# 20160428.net
KiCad netlist of a schematic drawn in Altium Designer
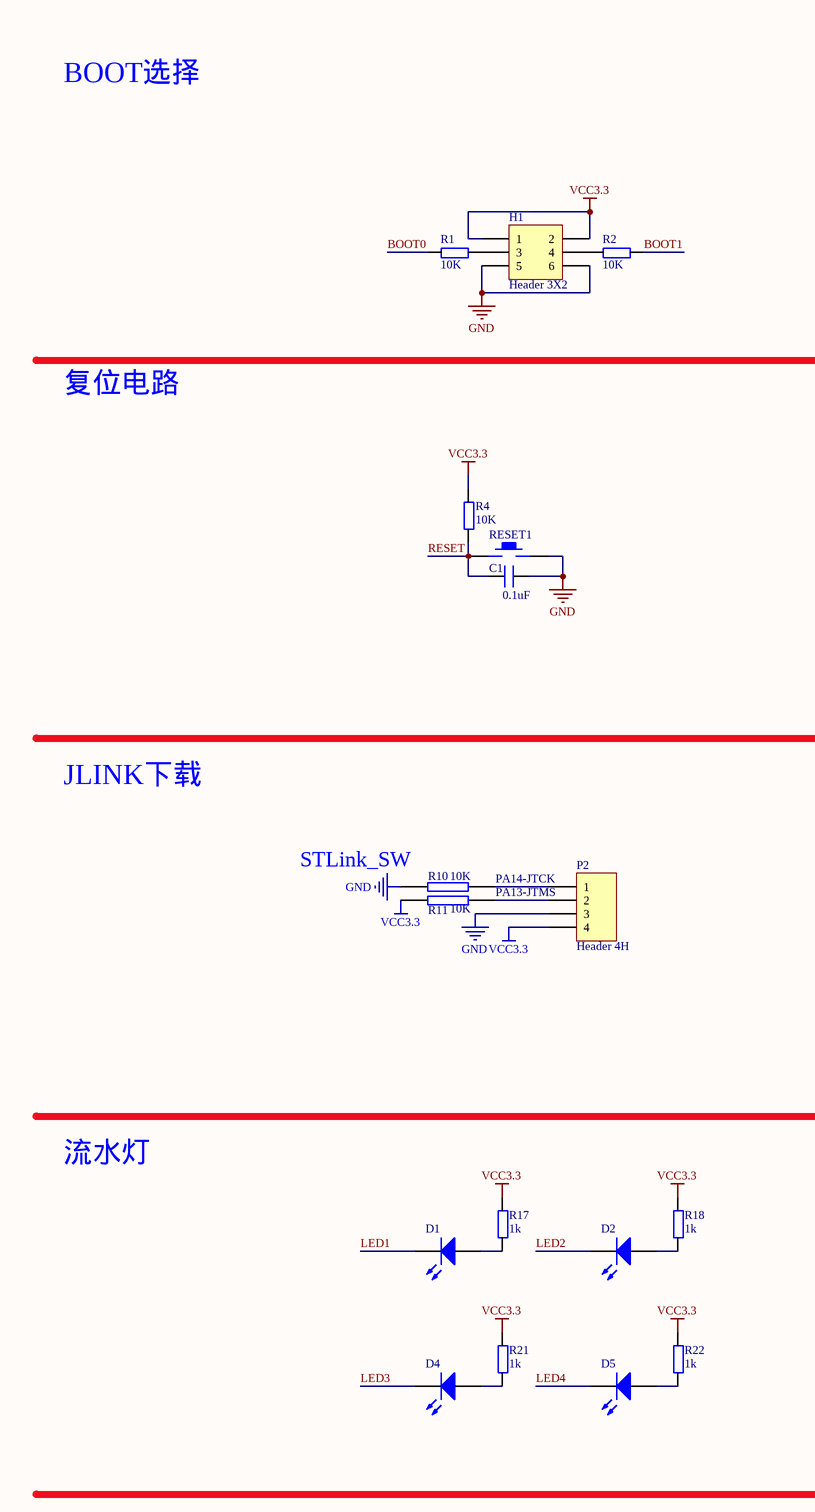
[diagram p0: 主控板20160428.SchDoc, top left]
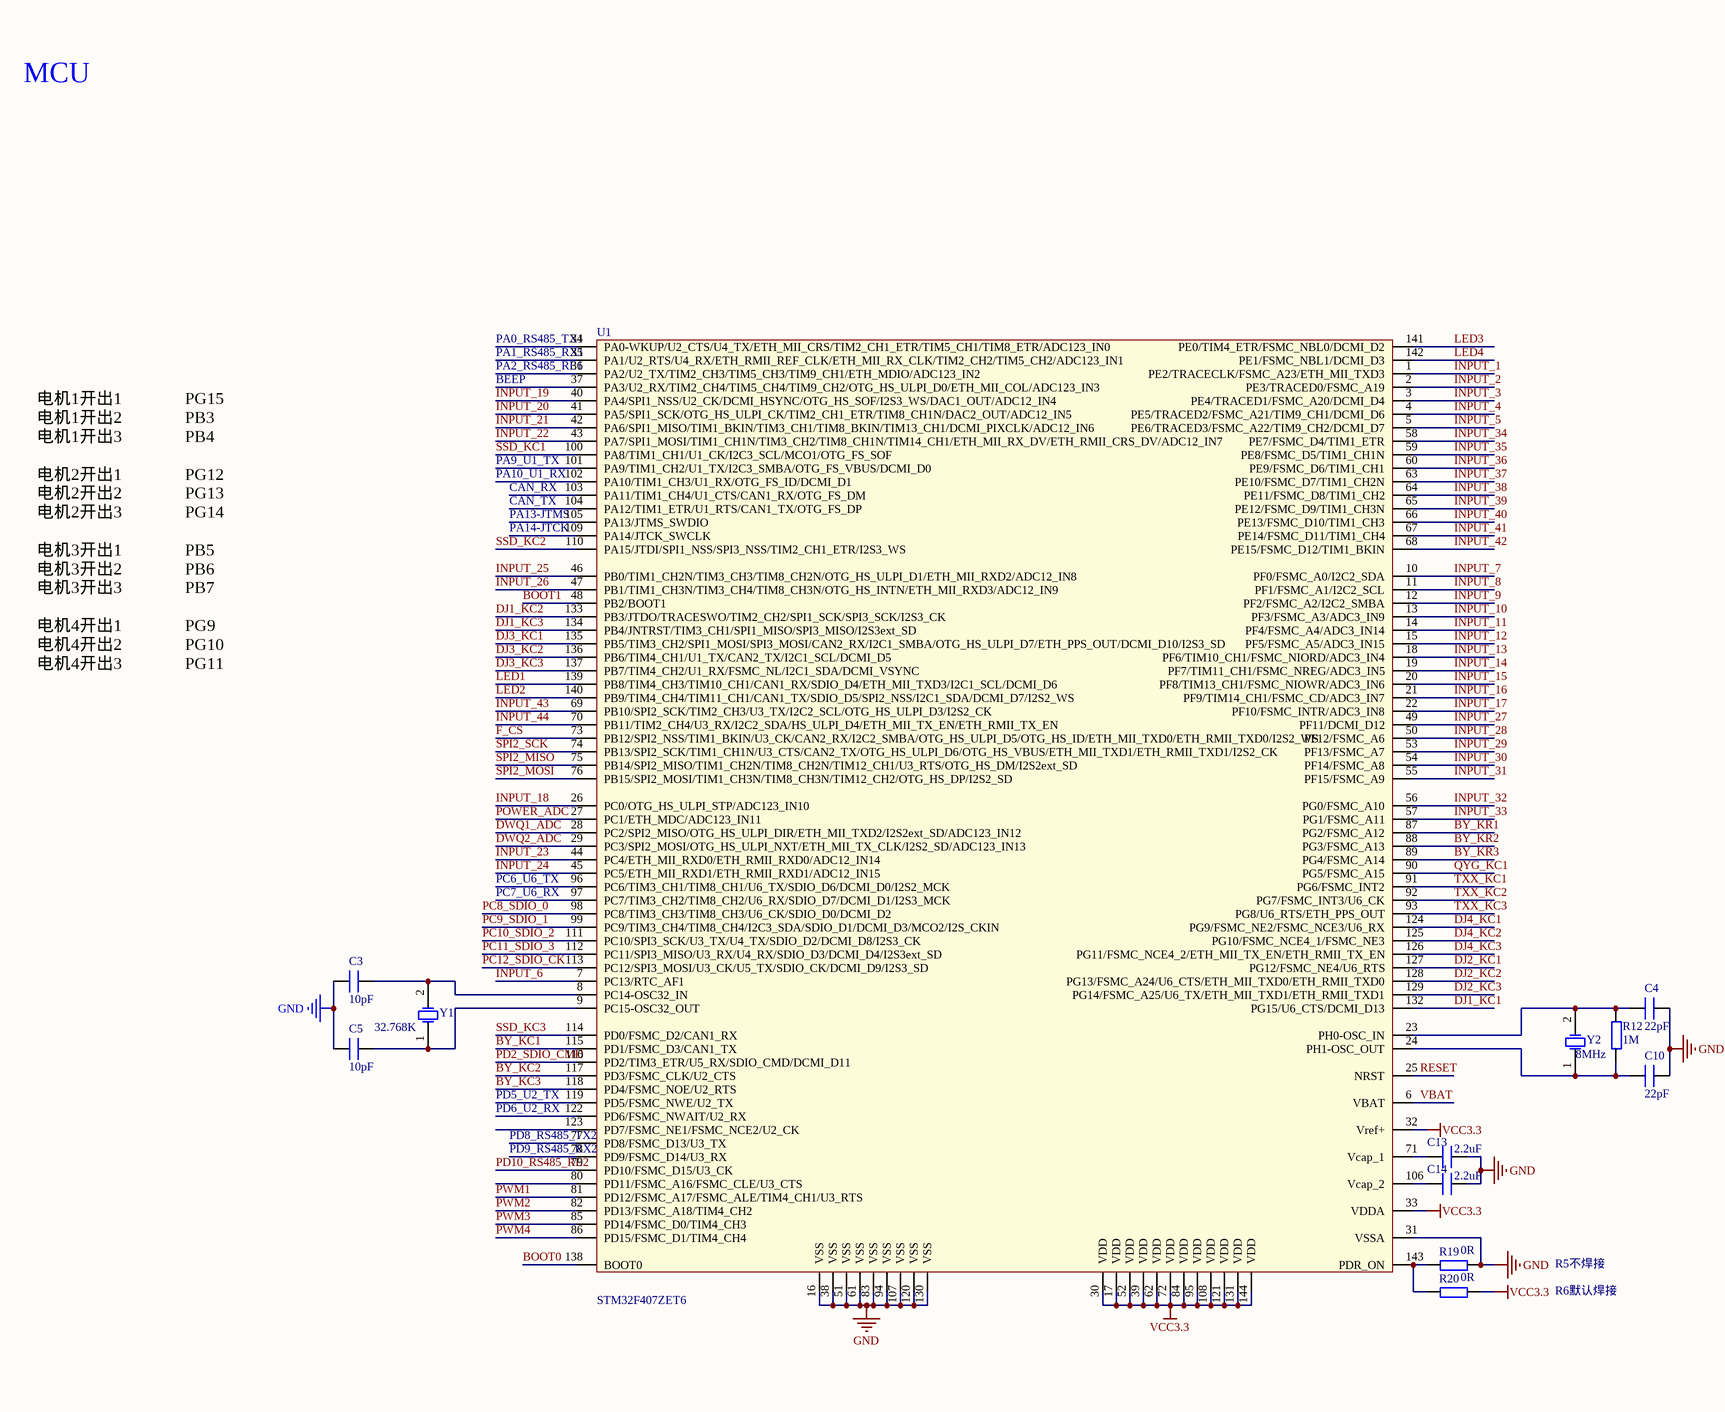
[diagram p1: 主控板20160428.SchDoc, top middle]
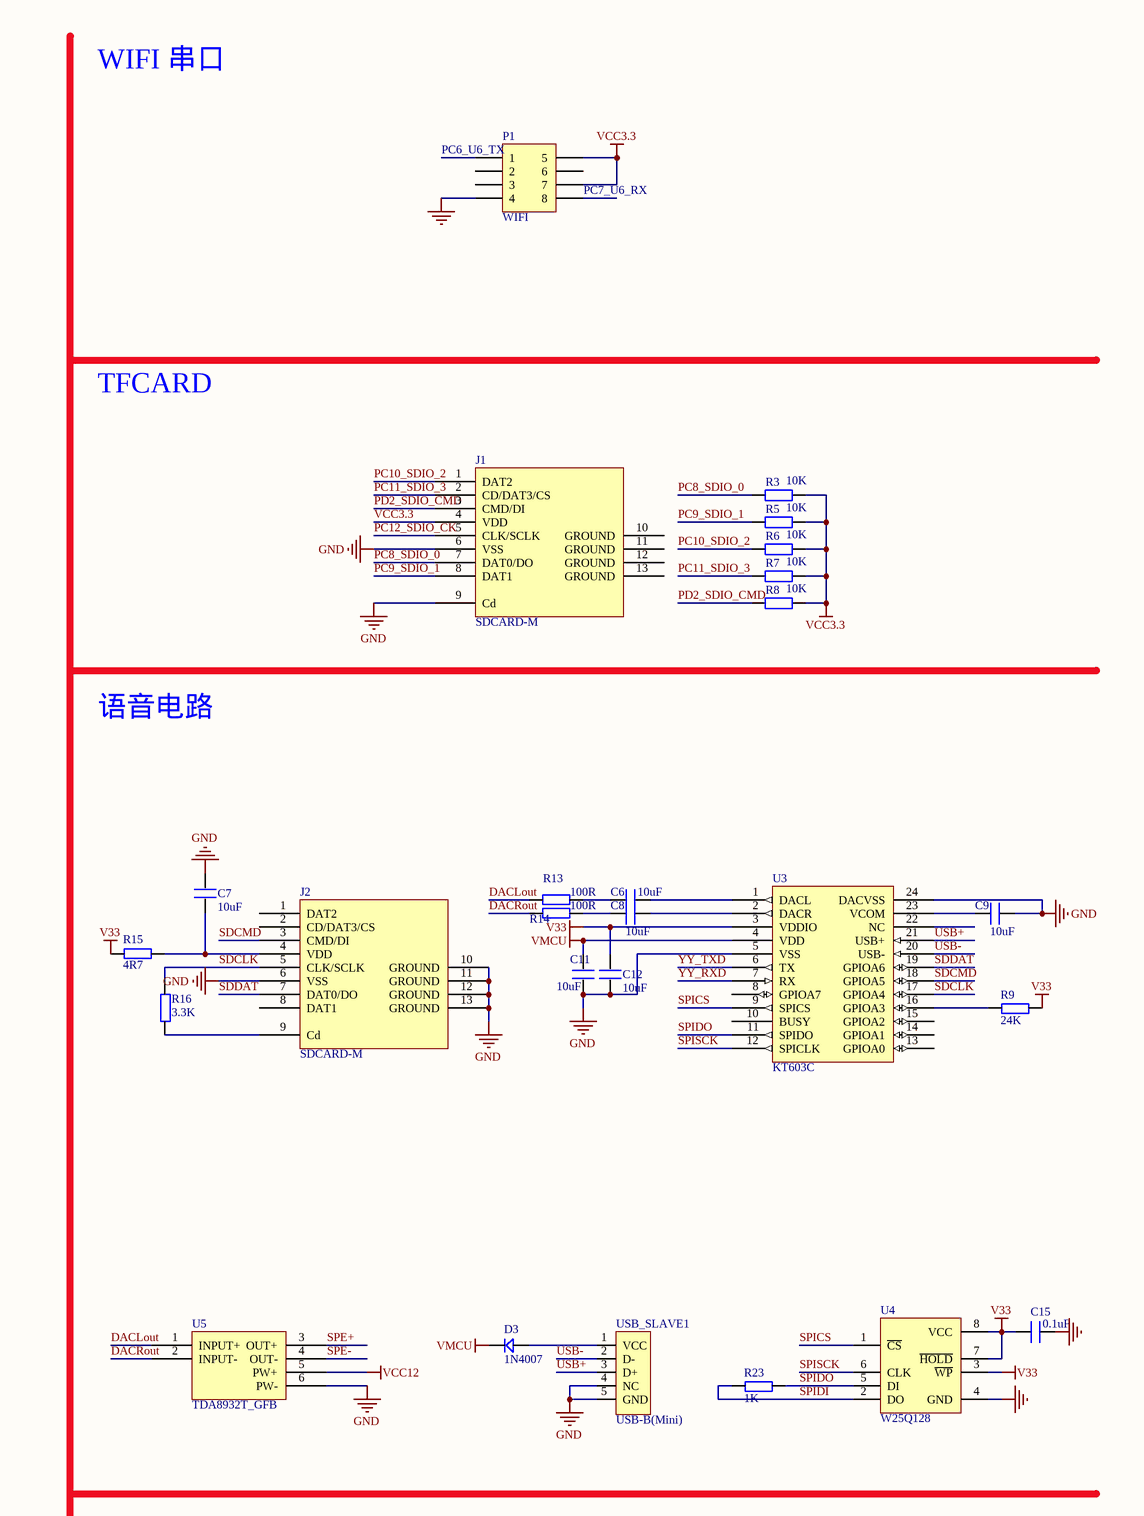
[diagram p2: 主控板20160428.SchDoc, top right]
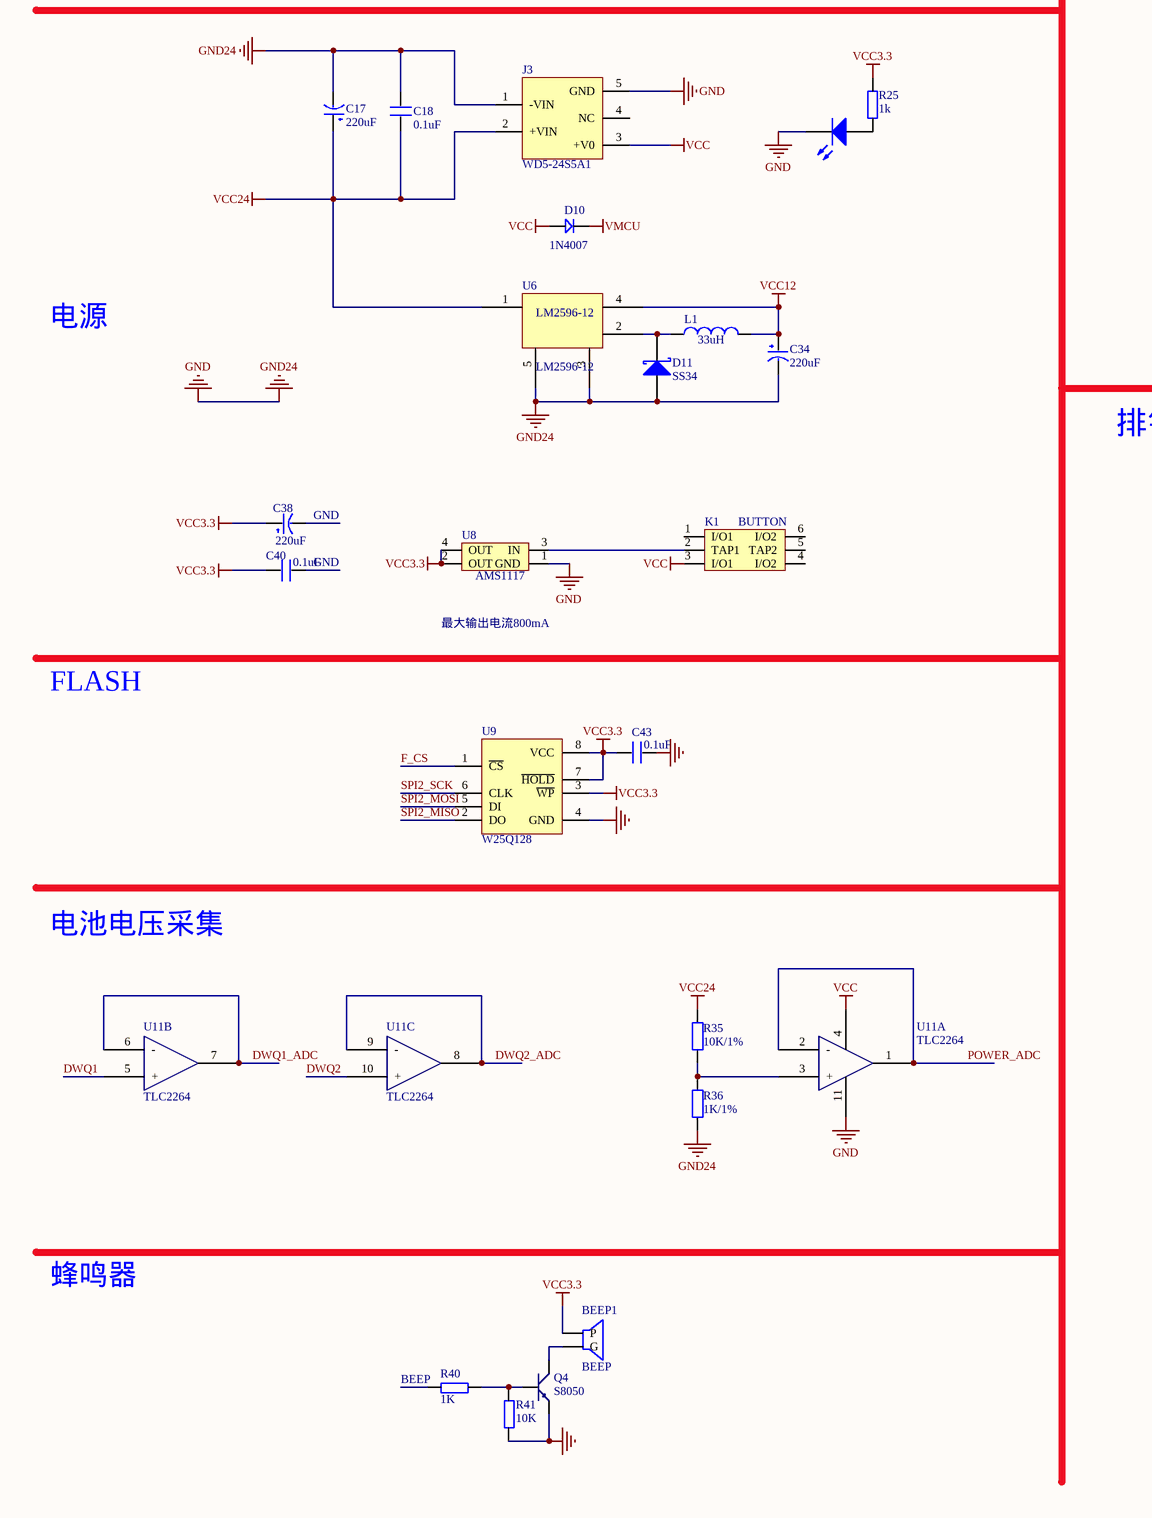
[diagram p3: 主控板20160428.SchDoc, bottom left]
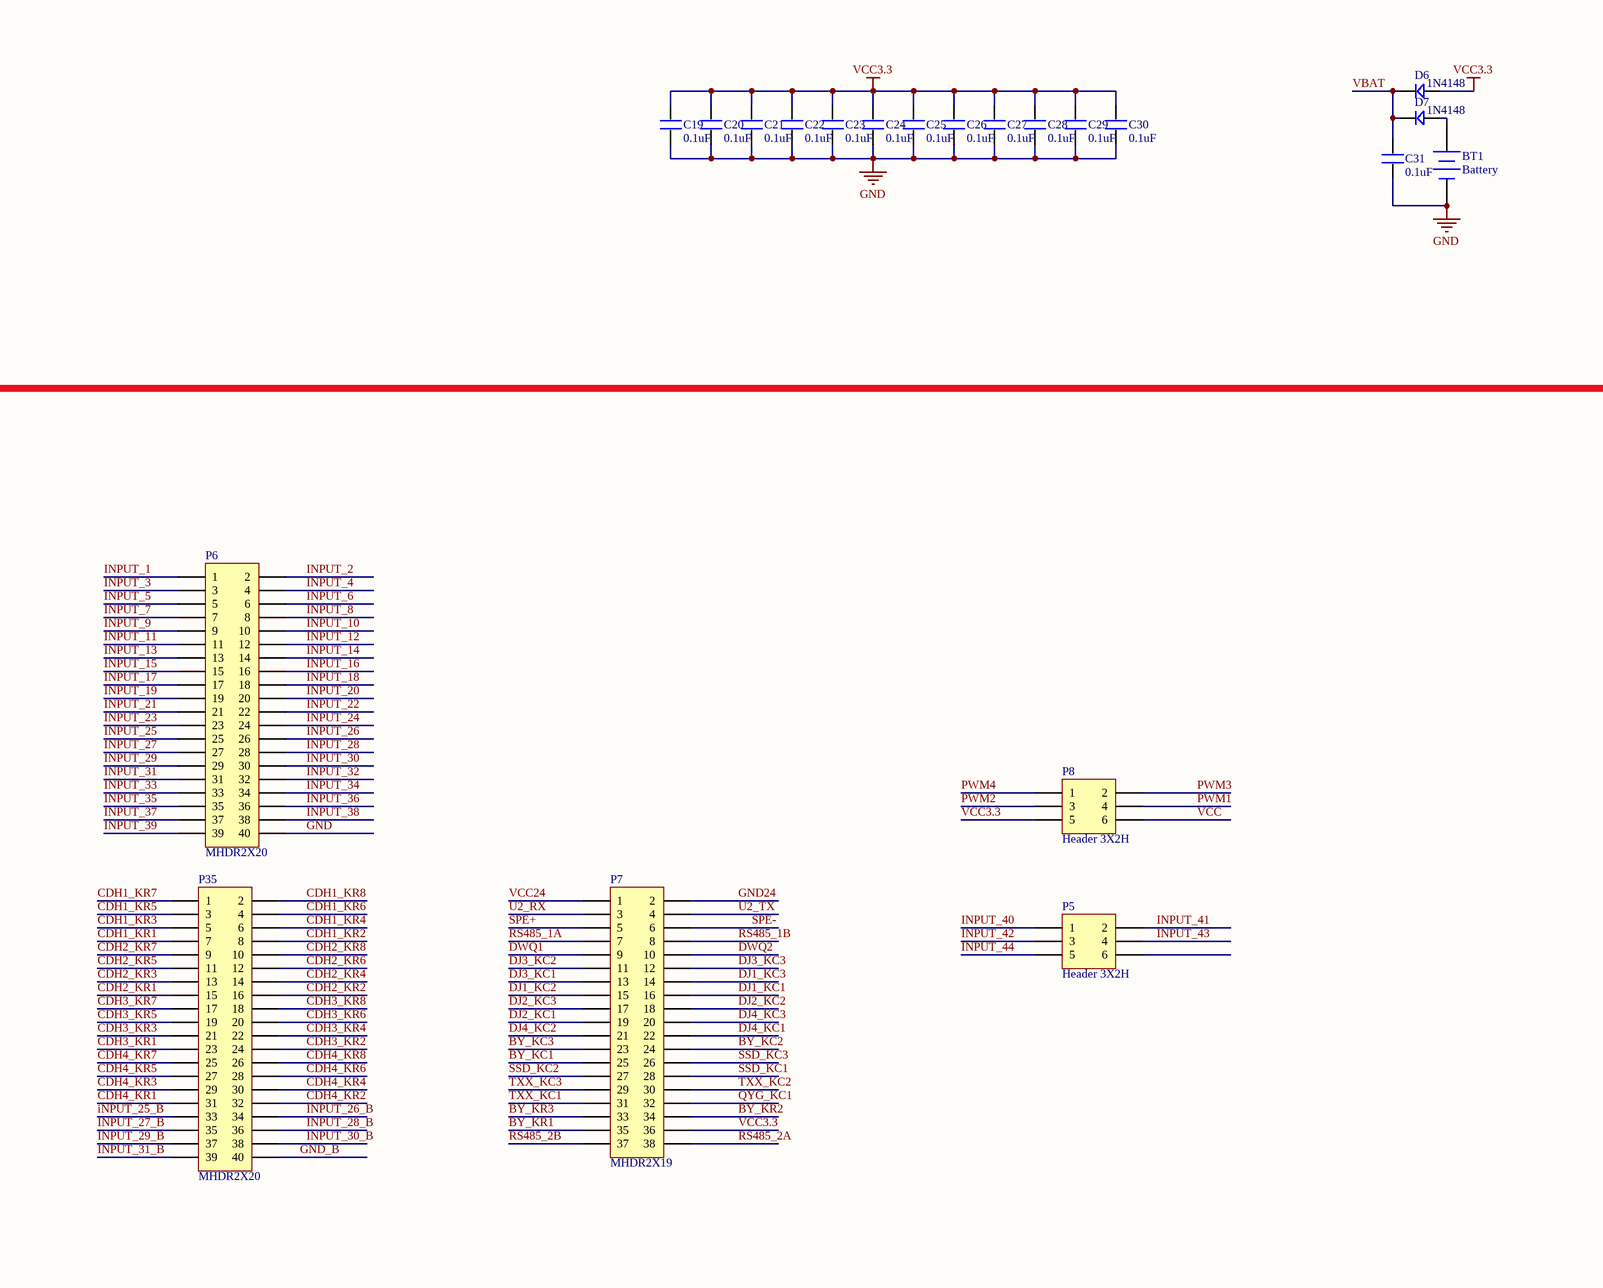
[diagram p4: 主控板20160428.SchDoc, bottom middle]
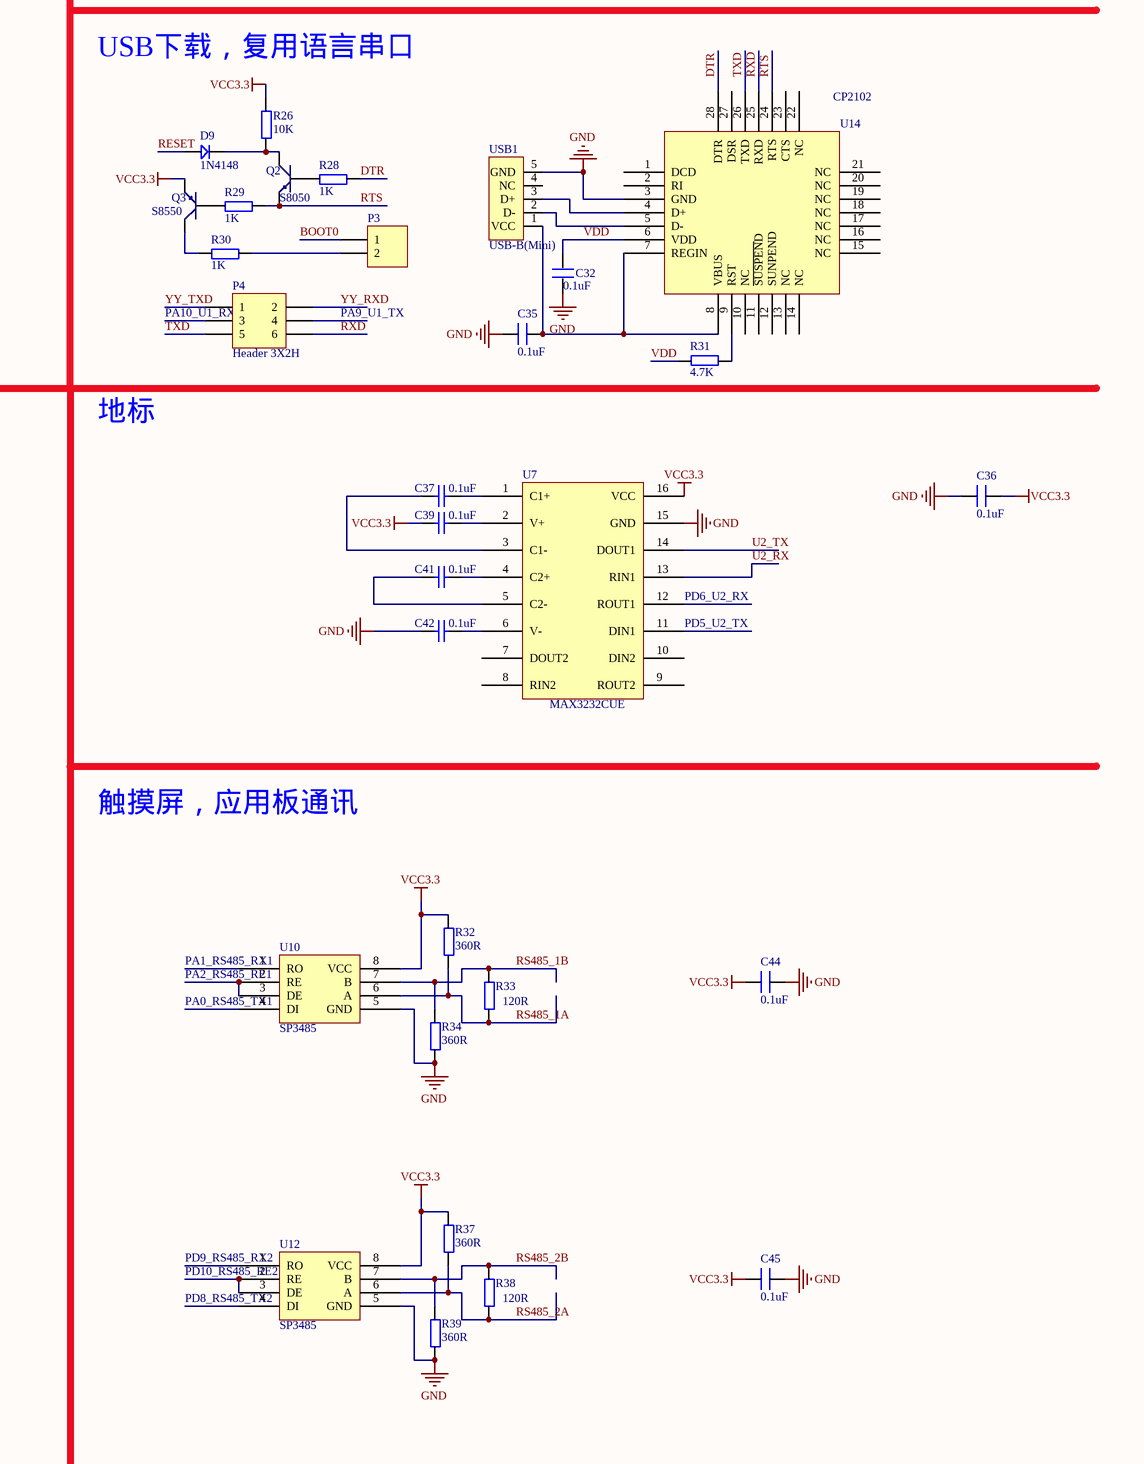
[diagram p5: 主控板20160428.SchDoc, bottom right]

(export (version "E")
  (design (tool "Eeschema 10.0.6"))
  (components
    (comp (ref "BEEP1") (value "BEEP") (footprint "BELL-5") (libsource (lib "WarShip V3_SCH") (part "BEEP")))
    (comp (ref "BT1")
      (value "Battery")
      (footprint "CR1220")
      (description "备份电池")
      (fields (field (name "PUBLISHER") "Altium Limited"))
      (libsource (lib "fszhang") (part "Battery"))
    )
    (comp (ref "C1") (value "0.1uF") (footprint "0805") (libsource (lib "Explorer STM32F407封装库") (part "C")))
    (comp (ref "C3") (value "10pF") (footprint "0805") (libsource (lib "Explorer STM32F407封装库") (part "C_2")))
    (comp (ref "C4") (value "22pF") (footprint "0805") (libsource (lib "Explorer STM32F407封装库") (part "C_3")))
    (comp (ref "C5") (value "10pF") (footprint "0805") (libsource (lib "Explorer STM32F407封装库") (part "C_2")))
    (comp (ref "C6") (value "10uF") (footprint "0805") (libsource (lib "WarShip V3_SCH") (part "C")))
    (comp (ref "C7") (value "10uF") (footprint "0805") (libsource (lib "WarShip V3_SCH") (part "C")))
    (comp (ref "C8") (value "10uF") (footprint "0805") (libsource (lib "WarShip V3_SCH") (part "C")))
    (comp (ref "C9") (value "10uF") (footprint "0805") (libsource (lib "WarShip V3_SCH") (part "C")))
    (comp (ref "C10")
      (value "22pF")
      (footprint "0805")
      (libsource (lib "Explorer STM32F407封装库") (part "C_3"))
    )
    (comp (ref "C11") (value "10uF") (footprint "0805") (libsource (lib "WarShip V3_SCH") (part "C")))
    (comp (ref "C12") (value "10uF") (footprint "0805") (libsource (lib "WarShip V3_SCH") (part "C")))
    (comp (ref "C13") (value "2.2uF") (footprint "0805") (libsource (lib "Explorer STM32F407封装库") (part "C")))
    (comp (ref "C14") (value "2.2uF") (footprint "0805") (libsource (lib "Explorer STM32F407封装库") (part "C")))
    (comp (ref "C15") (value "0.1uF") (footprint "0805") (libsource (lib "WarShip V3_SCH") (part "C")))
    (comp (ref "C17") (value "220uF") (footprint "CC6.56.5") (libsource (lib "WarShip V3_SCH") (part "CAP")))
    (comp (ref "C18") (value "0.1uF") (footprint "0805") (libsource (lib "WarShip V3_SCH") (part "C")))
    (comp (ref "C19") (value "0.1uF") (footprint "0805") (libsource (lib "WarShip V3_SCH") (part "C")))
    (comp (ref "C20") (value "0.1uF") (footprint "0805") (libsource (lib "WarShip V3_SCH") (part "C")))
    (comp (ref "C21") (value "0.1uF") (footprint "0805") (libsource (lib "WarShip V3_SCH") (part "C")))
    (comp (ref "C22") (value "0.1uF") (footprint "0805") (libsource (lib "WarShip V3_SCH") (part "C")))
    (comp (ref "C23") (value "0.1uF") (footprint "0805") (libsource (lib "WarShip V3_SCH") (part "C")))
    (comp (ref "C24") (value "0.1uF") (footprint "0805") (libsource (lib "WarShip V3_SCH") (part "C")))
    (comp (ref "C25") (value "0.1uF") (footprint "0805") (libsource (lib "WarShip V3_SCH") (part "C")))
    (comp (ref "C26") (value "0.1uF") (footprint "0805") (libsource (lib "WarShip V3_SCH") (part "C")))
    (comp (ref "C27") (value "0.1uF") (footprint "0805") (libsource (lib "WarShip V3_SCH") (part "C")))
    (comp (ref "C28") (value "0.1uF") (footprint "0805") (libsource (lib "WarShip V3_SCH") (part "C")))
    (comp (ref "C29") (value "0.1uF") (footprint "0805") (libsource (lib "WarShip V3_SCH") (part "C")))
    (comp (ref "C30") (value "0.1uF") (footprint "0805") (libsource (lib "WarShip V3_SCH") (part "C")))
    (comp (ref "C31")
      (value "0.1uF")
      (footprint "0805")
      (libsource (lib "Explorer STM32F407封装库") (part "C_3"))
    )
    (comp (ref "C32")
      (value "0.1uF")
      (footprint "0805")
      (libsource (lib "Explorer STM32F407封装库") (part "C_2"))
    )
    (comp (ref "C34") (value "220uF") (footprint "CC6.56.5") (libsource (lib "WarShip V3_SCH") (part "CAP")))
    (comp (ref "C35")
      (value "0.1uF")
      (footprint "0805")
      (libsource (lib "Explorer STM32F407封装库") (part "C_2"))
    )
    (comp (ref "C36")
      (value "0.1uF")
      (footprint "0805")
      (libsource (lib "Explorer STM32F407封装库") (part "C_2"))
    )
    (comp (ref "C37")
      (value "0.1uF")
      (footprint "0805")
      (description "Capacitor")
      (fields (field (name "PUBLISHER") "Altium Limited"))
      (libsource (lib "Miscellaneous Devices") (part "Cap"))
    )
    (comp (ref "C38") (value "220uF") (footprint "CC6.56.5") (libsource (lib "WarShip V3_SCH") (part "CAP")))
    (comp (ref "C39")
      (value "0.1uF")
      (footprint "0805")
      (description "Capacitor")
      (fields (field (name "PUBLISHER") "Altium Limited"))
      (libsource (lib "Miscellaneous Devices") (part "Cap"))
    )
    (comp (ref "C40") (value "0.1uF") (footprint "0805") (libsource (lib "WarShip V3_SCH") (part "C")))
    (comp (ref "C41")
      (value "0.1uF")
      (footprint "0805")
      (description "Capacitor")
      (fields (field (name "PUBLISHER") "Altium Limited"))
      (libsource (lib "Miscellaneous Devices") (part "Cap"))
    )
    (comp (ref "C42")
      (value "0.1uF")
      (footprint "0805")
      (description "Capacitor")
      (fields (field (name "PUBLISHER") "Altium Limited"))
      (libsource (lib "Miscellaneous Devices") (part "Cap"))
    )
    (comp (ref "C43") (value "0.1uF") (footprint "0805") (libsource (lib "WarShip V3_SCH") (part "C")))
    (comp (ref "C44")
      (value "0.1uF")
      (footprint "0805")
      (libsource (lib "Explorer STM32F407封装库") (part "C_3"))
    )
    (comp (ref "C45")
      (value "0.1uF")
      (footprint "0805")
      (libsource (lib "Explorer STM32F407封装库") (part "C_3"))
    )
    (comp (ref "D1")
      (value "~")
      (footprint "LED")
      (description "Typical RED, GREEN, YELLOW, AMBER GaAs LED")
      (fields (field (name "PUBLISHER") "Altium Limited"))
      (libsource (lib "Explorer STM32F407封装库") (part "LED2"))
    )
    (comp (ref "D2")
      (value "~")
      (footprint "LED")
      (description "Typical RED, GREEN, YELLOW, AMBER GaAs LED")
      (fields (field (name "PUBLISHER") "Altium Limited"))
      (libsource (lib "Explorer STM32F407封装库") (part "LED2"))
    )
    (comp (ref "D3")
      (value "1N4007")
      (footprint "DIDOE")
      (libsource (lib "Explorer STM32F407封装库") (part "D"))
    )
    (comp (ref "D4")
      (value "~")
      (footprint "LED")
      (description "Typical RED, GREEN, YELLOW, AMBER GaAs LED")
      (fields (field (name "PUBLISHER") "Altium Limited"))
      (libsource (lib "Explorer STM32F407封装库") (part "LED2"))
    )
    (comp (ref "D5")
      (value "~")
      (footprint "LED")
      (description "Typical RED, GREEN, YELLOW, AMBER GaAs LED")
      (fields (field (name "PUBLISHER") "Altium Limited"))
      (libsource (lib "Explorer STM32F407封装库") (part "LED2"))
    )
    (comp (ref "D6")
      (value "1N4148")
      (footprint "DIDOE")
      (libsource (lib "Explorer STM32F407封装库") (part "D"))
    )
    (comp (ref "D7")
      (value "1N4148")
      (footprint "DIDOE")
      (libsource (lib "Explorer STM32F407封装库") (part "D"))
    )
    (comp (ref "D8")
      (value "~")
      (footprint "LED")
      (description "Typical RED, GREEN, YELLOW, AMBER GaAs LED")
      (fields (field (name "PUBLISHER") "Altium Limited"))
      (libsource (lib "Explorer STM32F407封装库") (part "LED2"))
    )
    (comp (ref "D9") (value "1N4148") (footprint "DIDOE") (libsource (lib "WarShip V3_SCH") (part "D")))
    (comp (ref "D10")
      (value "1N4007")
      (footprint "DIDOE")
      (libsource (lib "Explorer STM32F407封装库") (part "D"))
    )
    (comp (ref "D11")
      (value "SS34")
      (footprint "SS34")
      (description "Silicon RF Schottky Diode for Mixer Applications in the VHF/UHF Range")
      (fields (field (name "PUBLISHER") "Altium Limited"))
      (libsource (lib "Miscellaneous Devices") (part "Diode BAT17"))
    )
    (comp (ref "H1")
      (value "Header 3X2")
      (footprint "HDR2X3")
      (description "Header, 3-Pin, Dual row")
      (fields (field (name "PUBLISHER") "Altium Limited"))
      (libsource (lib "Explorer STM32F407封装库") (part "Header 3X2"))
    )
    (comp (ref "J1")
      (value "SDCARD-M")
      (footprint "SDCARD-M")
      (description "TF卡槽")
      (libsource (lib "fszhang") (part "SDCARD-M"))
    )
    (comp (ref "J2")
      (value "SDCARD-M")
      (footprint "SDCARD-M")
      (description "TF卡槽")
      (libsource (lib "fszhang") (part "SDCARD-M"))
    )
    (comp (ref "J3")
      (value "WD5-24S5A1")
      (footprint "WD5-24S3V3")
      (libsource (lib "*") (part "WD5-24S3V3A1"))
    )
    (comp (ref "K1")
      (value "BUTTON")
      (footprint "BTN8.5*8.5")
      (libsource (lib "WarShip V3_SCH") (part "BUTTON"))
    )
    (comp (ref "L1")
      (value "33uH")
      (footprint "L-330")
      (description "Inductor")
      (fields (field (name "PUBLISHER") "Altium Limited"))
      (libsource (lib "Miscellaneous Devices") (part "Inductor"))
    )
    (comp (ref "P1")
      (value "WIFI")
      (footprint "HDR2X4_CEN")
      (description "Header, 4-Pin, Dual row")
      (fields (field (name "PUBLISHER") "Altium Limited"))
      (libsource (lib "Miscellaneous Connectors") (part "Header 4X2A"))
    )
    (comp (ref "P2")
      (value "Header 4H")
      (footprint "HDR1X4")
      (description "Header, 4-Pin, Right Angle")
      (fields (field (name "PUBLISHER") "Altium Limited"))
      (libsource (lib "Miscellaneous Connectors") (part "Header 4H"))
    )
    (comp (ref "P3")
      (value "Header 2")
      (footprint "HDR1X2")
      (description "Header, 2-Pin")
      (fields (field (name "PUBLISHER") "Altium Limited"))
      (libsource (lib "Miscellaneous Connectors") (part "Header 2"))
    )
    (comp (ref "P4")
      (value "Header 3X2H")
      (footprint "HDR2X3")
      (description "Header, 3-Pin, Dual row, Right Angle")
      (fields (field (name "PUBLISHER") "Altium Limited"))
      (libsource (lib "Miscellaneous Connectors") (part "Header 3X2H"))
    )
    (comp (ref "P5")
      (value "Header 3X2H")
      (footprint "HDR2X3")
      (description "Header, 3-Pin, Dual row, Right Angle")
      (fields (field (name "PUBLISHER") "Altium Limited"))
      (libsource (lib "Miscellaneous Connectors") (part "Header 3X2H"))
    )
    (comp (ref "P6")
      (value "MHDR2X20")
      (footprint "DIP-2X20")
      (description "Header, 20-Pin, Dual row")
      (fields (field (name "PUBLISHER") "Altium Limited"))
      (libsource (lib "Miscellaneous Connectors") (part "MHDR2X20"))
    )
    (comp (ref "P7")
      (value "MHDR2X19")
      (footprint "DIP-2X19")
      (description "Header, 19-Pin, Dual row")
      (fields (field (name "PUBLISHER") "Altium Limited"))
      (libsource (lib "Miscellaneous Connectors") (part "MHDR2X19"))
    )
    (comp (ref "P8")
      (value "Header 3X2H")
      (footprint "HDR2X3")
      (description "Header, 3-Pin, Dual row, Right Angle")
      (fields (field (name "PUBLISHER") "Altium Limited"))
      (libsource (lib "Miscellaneous Connectors") (part "Header 3X2H"))
    )
    (comp (ref "P35")
      (value "MHDR2X20")
      (footprint "DIP-2X20")
      (description "Header, 20-Pin, Dual row")
      (fields (field (name "PUBLISHER") "Altium Limited"))
      (libsource (lib "Miscellaneous Connectors") (part "MHDR2X20"))
    )
    (comp (ref "Q2")
      (value "S8050")
      (footprint "SOT-23R")
      (description "8050/BCW846/BCW847")
      (libsource (lib "WarShip V3_SCH") (part "NPN"))
    )
    (comp (ref "Q3")
      (value "S8550")
      (footprint "SOT-23R")
      (description "8550/BCW68")
      (libsource (lib "WarShip V3_SCH") (part "PNP"))
    )
    (comp (ref "Q4")
      (value "S8050")
      (footprint "SOT-23R")
      (description "8050/BCW846/BCW847")
      (libsource (lib "WarShip V3_SCH") (part "NPN"))
    )
    (comp (ref "R1") (value "10K") (footprint "0805") (libsource (lib "Explorer STM32F407封装库") (part "R_1")))
    (comp (ref "R2") (value "10K") (footprint "0805") (libsource (lib "Explorer STM32F407封装库") (part "R_1")))
    (comp (ref "R3")
      (value "10K")
      (footprint "0805")
      (description "贴片电阻")
      (fields (field (name "PUBLISHER") "Altium Limited"))
      (libsource (lib "fszhang") (part "Res1"))
    )
    (comp (ref "R4") (value "10K") (footprint "0805") (libsource (lib "Explorer STM32F407封装库") (part "R_2")))
    (comp (ref "R5")
      (value "10K")
      (footprint "0805")
      (description "贴片电阻")
      (fields (field (name "PUBLISHER") "Altium Limited"))
      (libsource (lib "fszhang") (part "Res1"))
    )
    (comp (ref "R6")
      (value "10K")
      (footprint "0805")
      (description "贴片电阻")
      (fields (field (name "PUBLISHER") "Altium Limited"))
      (libsource (lib "fszhang") (part "Res1"))
    )
    (comp (ref "R7")
      (value "10K")
      (footprint "0805")
      (description "贴片电阻")
      (fields (field (name "PUBLISHER") "Altium Limited"))
      (libsource (lib "fszhang") (part "Res1"))
    )
    (comp (ref "R8")
      (value "10K")
      (footprint "0805")
      (description "贴片电阻")
      (fields (field (name "PUBLISHER") "Altium Limited"))
      (libsource (lib "fszhang") (part "Res1"))
    )
    (comp (ref "R9") (value "24K") (footprint "0805") (libsource (lib "Explorer STM32F407封装库") (part "R_2")))
    (comp (ref "R10") (value "10K") (footprint "0805") (libsource (lib "*") (part "RES2")))
    (comp (ref "R11") (value "10K") (footprint "0805") (libsource (lib "*") (part "RES2")))
    (comp (ref "R12") (value "1M") (footprint "0805") (libsource (lib "Explorer STM32F407封装库") (part "R")))
    (comp (ref "R13")
      (value "100R")
      (footprint "0805")
      (libsource (lib "Explorer STM32F407封装库") (part "R_2"))
    )
    (comp (ref "R14")
      (value "100R")
      (footprint "0805")
      (libsource (lib "Explorer STM32F407封装库") (part "R_2"))
    )
    (comp (ref "R15") (value "4R7") (footprint "0805") (libsource (lib "Explorer STM32F407封装库") (part "R_2")))
    (comp (ref "R16")
      (value "3.3K")
      (footprint "0805")
      (libsource (lib "Explorer STM32F407封装库") (part "R_2"))
    )
    (comp (ref "R17") (value "1k") (footprint "0805") (libsource (lib "Explorer STM32F407封装库") (part "R_2")))
    (comp (ref "R18") (value "1k") (footprint "0805") (libsource (lib "Explorer STM32F407封装库") (part "R_2")))
    (comp (ref "R19") (value "0R") (footprint "0805") (libsource (lib "Explorer STM32F407封装库") (part "R_2")))
    (comp (ref "R20") (value "0R") (footprint "0805") (libsource (lib "Explorer STM32F407封装库") (part "R_2")))
    (comp (ref "R21") (value "1k") (footprint "0805") (libsource (lib "Explorer STM32F407封装库") (part "R_2")))
    (comp (ref "R22") (value "1k") (footprint "0805") (libsource (lib "Explorer STM32F407封装库") (part "R_2")))
    (comp (ref "R23") (value "1K") (footprint "0805") (libsource (lib "Explorer STM32F407封装库") (part "R_2")))
    (comp (ref "R25") (value "1k") (footprint "0805") (libsource (lib "Explorer STM32F407封装库") (part "R_2")))
    (comp (ref "R26") (value "10K") (footprint "0805") (libsource (lib "WarShip V3_SCH") (part "R")))
    (comp (ref "R28") (value "1K") (footprint "0805") (libsource (lib "WarShip V3_SCH") (part "R")))
    (comp (ref "R29") (value "1K") (footprint "0805") (libsource (lib "WarShip V3_SCH") (part "R")))
    (comp (ref "R30") (value "1K") (footprint "0805") (libsource (lib "WarShip V3_SCH") (part "R")))
    (comp (ref "R31") (value "4.7K") (footprint "0805") (libsource (lib "WarShip V3_SCH") (part "R")))
    (comp (ref "R32")
      (value "360R")
      (footprint "0805")
      (libsource (lib "Explorer STM32F407封装库") (part "R_2"))
    )
    (comp (ref "R33")
      (value "120R")
      (footprint "0805")
      (libsource (lib "Explorer STM32F407封装库") (part "R_2"))
    )
    (comp (ref "R34")
      (value "360R")
      (footprint "0805")
      (libsource (lib "Explorer STM32F407封装库") (part "R_2"))
    )
    (comp (ref "R35")
      (value "10K/1%")
      (footprint "0805")
      (description "Resistor")
      (fields (field (name "PUBLISHER") "Altium Limited"))
      (libsource (lib "Miscellaneous Devices") (part "Res2"))
    )
    (comp (ref "R36")
      (value "1K/1%")
      (footprint "0805")
      (description "Resistor")
      (fields (field (name "PUBLISHER") "Altium Limited"))
      (libsource (lib "Miscellaneous Devices") (part "Res2"))
    )
    (comp (ref "R37")
      (value "360R")
      (footprint "0805")
      (libsource (lib "Explorer STM32F407封装库") (part "R_2"))
    )
    (comp (ref "R38")
      (value "120R")
      (footprint "0805")
      (libsource (lib "Explorer STM32F407封装库") (part "R_2"))
    )
    (comp (ref "R39")
      (value "360R")
      (footprint "0805")
      (libsource (lib "Explorer STM32F407封装库") (part "R_2"))
    )
    (comp (ref "R40") (value "1K") (footprint "0805") (libsource (lib "WarShip V3_SCH") (part "R")))
    (comp (ref "R41") (value "10K") (footprint "0805") (libsource (lib "WarShip V3_SCH") (part "R")))
    (comp (ref "RESET1")
      (value "KEY_M")
      (footprint "SW_PB2_A1")
      (libsource (lib "Explorer STM32F407封装库") (part "KEY_M"))
    )
    (comp (ref "U1")
      (value "STM32F407ZET6")
      (footprint "LQFP144")
      (libsource (lib "Explorer STM32F407封装库") (part "STM32F407ZET6"))
    )
    (comp (ref "U3") (value "KT603C") (footprint "SSOP24") (libsource (lib "EXPLORER") (part "KT603C")))
    (comp (ref "U4")
      (value "W25Q128")
      (footprint "SOIC8_W")
      (description "SPI FLASH")
      (libsource (lib "fszhang") (part "W25QXX"))
    )
    (comp (ref "U5")
      (value "TDA8932T_GFB")
      (footprint "TDA8932T_GFB")
      (libsource (lib "EXPLORER") (part "TDA8932T_GFB"))
    )
    (comp (ref "U6")
      (value "LM2596-12")
      (footprint "LM2596-12")
      (libsource (lib "EXPLORER") (part "LM2596-12V"))
    )
    (comp (ref "U7")
      (value "MAX3232CUE")
      (footprint "SO-16")
      (libsource (lib "Smart_board_v1") (part "MAX3232CUE"))
    )
    (comp (ref "U8")
      (value "AMS1117")
      (footprint "SOT-223")
      (libsource (lib "WarShip V3_SCH") (part "AMS1117"))
    )
    (comp (ref "U9")
      (value "W25Q128")
      (footprint "SOIC8_W")
      (description "SPI FLASH")
      (libsource (lib "fszhang") (part "W25QXX"))
    )
    (comp (ref "U10") (value "SP3485") (footprint "SO-8") (libsource (lib "Schlib1") (part "SP3485")))
    (comp (ref "U11") (value "TLC2264") (footprint "SO-14") (libsource (lib "EXPLORER") (part "TLC2264")))
    (comp (ref "U12") (value "SP3485") (footprint "SO-8") (libsource (lib "Schlib1") (part "SP3485")))
    (comp (ref "U14") (value "CP2102") (footprint "QFN28") (libsource (lib "Schlib1") (part "CP2102")))
    (comp (ref "USB1")
      (value "USB-B(Mini)")
      (footprint "PCBComponent_1 - duplicate")
      (libsource (lib "") (part "USB5_1"))
    )
    (comp (ref "USB_SLAVE1")
      (value "USB-B(Mini)")
      (footprint "PCBComponent_1 - duplicate")
      (libsource (lib "Explorer STM32F407封装库") (part "USB5"))
    )
    (comp (ref "Y1")
      (value "32.768K")
      (footprint "XTAL32")
      (description "Crystal Oscillator")
      (fields (field (name "PUBLISHER") "Altium Limited"))
      (libsource (lib "Explorer STM32F407封装库") (part "XTAL_1"))
    )
    (comp (ref "Y2")
      (value "8MHz")
      (footprint "XTAL_US")
      (description "Crystal Oscillator")
      (fields (field (name "PUBLISHER") "Altium Limited"))
      (libsource (lib "Explorer STM32F407封装库") (part "XTAL"))
    )
  )
  (nets
    (net (code "1") (name "/BEEP") (class "Default")
      (node (ref "R40") (pin "1") (pintype "passive"))
      (node (ref "U1") (pin "37") (pinfunction "PA3/U2_RX/TIM2_CH4/TIM5_CH4/TIM9_CH2/OTG_HS_ULPI_D0/ETH_MII_COL/ADC123_IN3_37") (pintype "passive"))
    )
    (net (code "2") (name "/BOOT0") (class "Default")
      (node (ref "P3") (pin "1") (pinfunction "1_1") (pintype "passive"))
      (node (ref "R1") (pin "1") (pintype "passive"))
      (node (ref "U1") (pin "138") (pinfunction "BOOT0_138") (pintype "passive"))
    )
    (net (code "3") (name "/BOOT1") (class "Default")
      (node (ref "R2") (pin "2") (pintype "passive"))
      (node (ref "U1") (pin "48") (pinfunction "PB2/BOOT1_48") (pintype "passive"))
    )
    (net (code "4") (name "/BY_KC1") (class "Default")
      (node (ref "P7") (pin "25") (pinfunction "25_25") (pintype "passive"))
      (node (ref "U1") (pin "115") (pinfunction "PD1/FSMC_D3/CAN1_TX_115") (pintype "passive"))
    )
    (net (code "5") (name "/BY_KC2") (class "Default")
      (node (ref "P7") (pin "24") (pinfunction "24_24") (pintype "passive"))
      (node (ref "U1") (pin "117") (pinfunction "PD3/FSMC_CLK/U2_CTS_117") (pintype "passive"))
    )
    (net (code "6") (name "/BY_KC3") (class "Default")
      (node (ref "P7") (pin "23") (pinfunction "23_23") (pintype "passive"))
      (node (ref "U1") (pin "118") (pinfunction "PD4/FSMC_NOE/U2_RTS_118") (pintype "passive"))
    )
    (net (code "7") (name "/BY_KR1") (class "Default")
      (node (ref "P7") (pin "35") (pinfunction "35_35") (pintype "passive"))
      (node (ref "U1") (pin "87") (pinfunction "PG2/FSMC_A12_87") (pintype "passive"))
    )
    (net (code "8") (name "/BY_KR2") (class "Default")
      (node (ref "P7") (pin "34") (pinfunction "34_34") (pintype "passive"))
      (node (ref "U1") (pin "88") (pinfunction "PG3/FSMC_A13_88") (pintype "passive"))
    )
    (net (code "9") (name "/BY_KR3") (class "Default")
      (node (ref "P7") (pin "33") (pinfunction "33_33") (pintype "passive"))
      (node (ref "U1") (pin "89") (pinfunction "PG4/FSMC_A14_89") (pintype "passive"))
    )
    (net (code "10") (name "/CAN_RX") (class "Default")
      (node (ref "U1") (pin "103") (pinfunction "PA11/TIM1_CH4/U1_CTS/CAN1_RX/OTG_FS_DM_103") (pintype "passive"))
    )
    (net (code "11") (name "/CAN_TX") (class "Default")
      (node (ref "U1") (pin "104") (pinfunction "PA12/TIM1_ETR/U1_RTS/CAN1_TX/OTG_FS_DP_104") (pintype "passive"))
    )
    (net (code "12") (name "/CDH1_KR1") (class "Default")
      (node (ref "P35") (pin "7") (pinfunction "7_7") (pintype "passive"))
    )
    (net (code "13") (name "/CDH1_KR2") (class "Default")
      (node (ref "P35") (pin "8") (pinfunction "8_8") (pintype "passive"))
    )
    (net (code "14") (name "/CDH1_KR3") (class "Default")
      (node (ref "P35") (pin "5") (pinfunction "5_5") (pintype "passive"))
    )
    (net (code "15") (name "/CDH1_KR4") (class "Default")
      (node (ref "P35") (pin "6") (pinfunction "6_6") (pintype "passive"))
    )
    (net (code "16") (name "/CDH1_KR5") (class "Default")
      (node (ref "P35") (pin "3") (pinfunction "3_3") (pintype "passive"))
    )
    (net (code "17") (name "/CDH1_KR6") (class "Default")
      (node (ref "P35") (pin "4") (pinfunction "4_4") (pintype "passive"))
    )
    (net (code "18") (name "/CDH1_KR7") (class "Default")
      (node (ref "P35") (pin "1") (pinfunction "1_1") (pintype "passive"))
    )
    (net (code "19") (name "/CDH1_KR8") (class "Default")
      (node (ref "P35") (pin "2") (pinfunction "2_2") (pintype "passive"))
    )
    (net (code "20") (name "/CDH2_KR1") (class "Default")
      (node (ref "P35") (pin "15") (pinfunction "15_15") (pintype "passive"))
    )
    (net (code "21") (name "/CDH2_KR2") (class "Default")
      (node (ref "P35") (pin "16") (pinfunction "16_16") (pintype "passive"))
    )
    (net (code "22") (name "/CDH2_KR3") (class "Default")
      (node (ref "P35") (pin "13") (pinfunction "13_13") (pintype "passive"))
    )
    (net (code "23") (name "/CDH2_KR4") (class "Default")
      (node (ref "P35") (pin "14") (pinfunction "14_14") (pintype "passive"))
    )
    (net (code "24") (name "/CDH2_KR5") (class "Default")
      (node (ref "P35") (pin "11") (pinfunction "11_11") (pintype "passive"))
    )
    (net (code "25") (name "/CDH2_KR6") (class "Default")
      (node (ref "P35") (pin "12") (pinfunction "12_12") (pintype "passive"))
    )
    (net (code "26") (name "/CDH2_KR7") (class "Default")
      (node (ref "P35") (pin "9") (pinfunction "9_9") (pintype "passive"))
    )
    (net (code "27") (name "/CDH2_KR8") (class "Default")
      (node (ref "P35") (pin "10") (pinfunction "10_10") (pintype "passive"))
    )
    (net (code "28") (name "/CDH3_KR1") (class "Default")
      (node (ref "P35") (pin "23") (pinfunction "23_23") (pintype "passive"))
    )
    (net (code "29") (name "/CDH3_KR2") (class "Default")
      (node (ref "P35") (pin "24") (pinfunction "24_24") (pintype "passive"))
    )
    (net (code "30") (name "/CDH3_KR3") (class "Default")
      (node (ref "P35") (pin "21") (pinfunction "21_21") (pintype "passive"))
    )
    (net (code "31") (name "/CDH3_KR4") (class "Default")
      (node (ref "P35") (pin "22") (pinfunction "22_22") (pintype "passive"))
    )
    (net (code "32") (name "/CDH3_KR5") (class "Default")
      (node (ref "P35") (pin "19") (pinfunction "19_19") (pintype "passive"))
    )
    (net (code "33") (name "/CDH3_KR6") (class "Default")
      (node (ref "P35") (pin "20") (pinfunction "20_20") (pintype "passive"))
    )
    (net (code "34") (name "/CDH3_KR7") (class "Default")
      (node (ref "P35") (pin "17") (pinfunction "17_17") (pintype "passive"))
    )
    (net (code "35") (name "/CDH3_KR8") (class "Default")
      (node (ref "P35") (pin "18") (pinfunction "18_18") (pintype "passive"))
    )
    (net (code "36") (name "/CDH4_KR1") (class "Default")
      (node (ref "P35") (pin "31") (pinfunction "31_31") (pintype "passive"))
    )
    (net (code "37") (name "/CDH4_KR2") (class "Default")
      (node (ref "P35") (pin "32") (pinfunction "32_32") (pintype "passive"))
    )
    (net (code "38") (name "/CDH4_KR3") (class "Default")
      (node (ref "P35") (pin "29") (pinfunction "29_29") (pintype "passive"))
    )
    (net (code "39") (name "/CDH4_KR4") (class "Default")
      (node (ref "P35") (pin "30") (pinfunction "30_30") (pintype "passive"))
    )
    (net (code "40") (name "/CDH4_KR5") (class "Default")
      (node (ref "P35") (pin "27") (pinfunction "27_27") (pintype "passive"))
    )
    (net (code "41") (name "/CDH4_KR6") (class "Default")
      (node (ref "P35") (pin "28") (pinfunction "28_28") (pintype "passive"))
    )
    (net (code "42") (name "/CDH4_KR7") (class "Default")
      (node (ref "P35") (pin "25") (pinfunction "25_25") (pintype "passive"))
    )
    (net (code "43") (name "/CDH4_KR8") (class "Default")
      (node (ref "P35") (pin "26") (pinfunction "26_26") (pintype "passive"))
    )
    (net (code "44") (name "/DACLout") (class "Default")
      (node (ref "R13") (pin "2") (pintype "passive"))
      (node (ref "U5") (pin "1") (pinfunction "INPUT+_1") (pintype "passive"))
    )
    (net (code "45") (name "/DACRout") (class "Default")
      (node (ref "R14") (pin "2") (pintype "passive"))
      (node (ref "U5") (pin "2") (pinfunction "INPUT-_2") (pintype "passive"))
    )
    (net (code "46") (name "/DJ1_KC1") (class "Default")
      (node (ref "P7") (pin "16") (pinfunction "16_16") (pintype "passive"))
      (node (ref "U1") (pin "132") (pinfunction "PG15/U6_CTS/DCMI_D13_132") (pintype "passive"))
    )
    (net (code "47") (name "/DJ1_KC2") (class "Default")
      (node (ref "P7") (pin "15") (pinfunction "15_15") (pintype "passive"))
      (node (ref "U1") (pin "133") (pinfunction "PB3/JTDO/TRACESWO/TIM2_CH2/SPI1_SCK/SPI3_SCK/I2S3_CK_133") (pintype "passive"))
    )
    (net (code "48") (name "/DJ1_KC3") (class "Default")
      (node (ref "P7") (pin "14") (pinfunction "14_14") (pintype "passive"))
      (node (ref "U1") (pin "134") (pinfunction "PB4/JNTRST/TIM3_CH1/SPI1_MISO/SPI3_MISO/I2S3ext_SD_134") (pintype "passive"))
    )
    (net (code "49") (name "/DJ2_KC1") (class "Default")
      (node (ref "P7") (pin "19") (pinfunction "19_19") (pintype "passive"))
      (node (ref "U1") (pin "127") (pinfunction "PG12/FSMC_NE4/U6_RTS_127") (pintype "passive"))
    )
    (net (code "50") (name "/DJ2_KC2") (class "Default")
      (node (ref "P7") (pin "18") (pinfunction "18_18") (pintype "passive"))
      (node (ref "U1") (pin "128") (pinfunction "PG13/FSMC_A24/U6_CTS/ETH_MII_TXD0/ETH_RMII_TXD0_128") (pintype "passive"))
    )
    (net (code "51") (name "/DJ2_KC3") (class "Default")
      (node (ref "P7") (pin "17") (pinfunction "17_17") (pintype "passive"))
      (node (ref "U1") (pin "129") (pinfunction "PG14/FSMC_A25/U6_TX/ETH_MII_TXD1/ETH_RMII_TXD1_129") (pintype "passive"))
    )
    (net (code "52") (name "/DJ3_KC1") (class "Default")
      (node (ref "P7") (pin "13") (pinfunction "13_13") (pintype "passive"))
      (node (ref "U1") (pin "135") (pinfunction "PB5/TIM3_CH2/SPI1_MOSI/SPI3_MOSI/CAN2_RX/I2C1_SMBA/OTG_HS_ULPI_D7/ETH_PPS_OUT/DCMI_D10/I2S3_SD_135") (pintype "passive"))
    )
    (net (code "53") (name "/DJ3_KC2") (class "Default")
      (node (ref "P7") (pin "11") (pinfunction "11_11") (pintype "passive"))
      (node (ref "U1") (pin "136") (pinfunction "PB6/TIM4_CH1/U1_TX/CAN2_TX/I2C1_SCL/DCMI_D5_136") (pintype "passive"))
    )
    (net (code "54") (name "/DJ3_KC3") (class "Default")
      (node (ref "P7") (pin "12") (pinfunction "12_12") (pintype "passive"))
      (node (ref "U1") (pin "137") (pinfunction "PB7/TIM4_CH2/U1_RX/FSMC_NL/I2C1_SDA/DCMI_VSYNC_137") (pintype "passive"))
    )
    (net (code "55") (name "/DJ4_KC1") (class "Default")
      (node (ref "P7") (pin "22") (pinfunction "22_22") (pintype "passive"))
      (node (ref "U1") (pin "124") (pinfunction "PG9/FSMC_NE2/FSMC_NCE3/U6_RX_124") (pintype "passive"))
    )
    (net (code "56") (name "/DJ4_KC2") (class "Default")
      (node (ref "P7") (pin "21") (pinfunction "21_21") (pintype "passive"))
      (node (ref "U1") (pin "125") (pinfunction "PG10/FSMC_NCE4_1/FSMC_NE3_125") (pintype "passive"))
    )
    (net (code "57") (name "/DJ4_KC3") (class "Default")
      (node (ref "P7") (pin "20") (pinfunction "20_20") (pintype "passive"))
      (node (ref "U1") (pin "126") (pinfunction "PG11/FSMC_NCE4_2/ETH_MII_TX_EN/ETH_RMII_TX_EN_126") (pintype "passive"))
    )
    (net (code "58") (name "/DTR") (class "Default")
      (node (ref "R28") (pin "2") (pintype "passive"))
      (node (ref "U14") (pin "28") (pinfunction "DTR_28") (pintype "passive"))
    )
    (net (code "59") (name "/DWQ1") (class "Default")
      (node (ref "P7") (pin "9") (pinfunction "9_9") (pintype "passive"))
      (node (ref "U11") (pin "5") (pinfunction "+_5") (pintype "passive"))
    )
    (net (code "60") (name "/DWQ1_ADC") (class "Default")
      (node (ref "U1") (pin "28") (pinfunction "PC2/SPI2_MISO/OTG_HS_ULPI_DIR/ETH_MII_TXD2/I2S2ext_SD/ADC123_IN12_28") (pintype "passive"))
      (node (ref "U11") (pin "6") (pinfunction "-_6") (pintype "passive"))
      (node (ref "U11") (pin "7") (pinfunction "2OUT_7") (pintype "passive"))
    )
    (net (code "61") (name "/DWQ2") (class "Default")
      (node (ref "P7") (pin "10") (pinfunction "10_10") (pintype "passive"))
      (node (ref "U11") (pin "10") (pinfunction "+_10") (pintype "passive"))
    )
    (net (code "62") (name "/DWQ2_ADC") (class "Default")
      (node (ref "U1") (pin "29") (pinfunction "PC3/SPI2_MOSI/OTG_HS_ULPI_NXT/ETH_MII_TX_CLK/I2S2_SD/ADC123_IN13_29") (pintype "passive"))
      (node (ref "U11") (pin "8") (pinfunction "3OUT_8") (pintype "passive"))
      (node (ref "U11") (pin "9") (pinfunction "-_9") (pintype "passive"))
    )
    (net (code "63") (name "/F_CS") (class "Default")
      (node (ref "U1") (pin "73") (pinfunction "PB12/SPI2_NSS/TIM1_BKIN/U3_CK/CAN2_RX/I2C2_SMBA/OTG_HS_ULPI_D5/OTG_HS_ID/ETH_MII_TXD0/ETH_RMII_TXD0/I2S2_WS_73") (pintype "passive"))
      (node (ref "U9") (pin "1") (pinfunction "~{CS}_1") (pintype "passive"))
    )
    (net (code "64") (name "/GND_B") (class "Default")
      (node (ref "P35") (pin "40") (pinfunction "40_40") (pintype "passive"))
    )
    (net (code "65") (name "/INPUT_1") (class "Default")
      (node (ref "P6") (pin "1") (pinfunction "1_1") (pintype "passive"))
      (node (ref "U1") (pin "1") (pinfunction "PE2/TRACECLK/FSMC_A23/ETH_MII_TXD3_1") (pintype "passive"))
    )
    (net (code "66") (name "/INPUT_2") (class "Default")
      (node (ref "P6") (pin "2") (pinfunction "2_2") (pintype "passive"))
      (node (ref "U1") (pin "2") (pinfunction "PE3/TRACED0/FSMC_A19_2") (pintype "passive"))
    )
    (net (code "67") (name "/INPUT_3") (class "Default")
      (node (ref "P6") (pin "3") (pinfunction "3_3") (pintype "passive"))
      (node (ref "U1") (pin "3") (pinfunction "PE4/TRACED1/FSMC_A20/DCMI_D4_3") (pintype "passive"))
    )
    (net (code "68") (name "/INPUT_4") (class "Default")
      (node (ref "P6") (pin "4") (pinfunction "4_4") (pintype "passive"))
      (node (ref "U1") (pin "4") (pinfunction "PE5/TRACED2/FSMC_A21/TIM9_CH1/DCMI_D6_4") (pintype "passive"))
    )
    (net (code "69") (name "/INPUT_5") (class "Default")
      (node (ref "P6") (pin "5") (pinfunction "5_5") (pintype "passive"))
      (node (ref "U1") (pin "5") (pinfunction "PE6/TRACED3/FSMC_A22/TIM9_CH2/DCMI_D7_5") (pintype "passive"))
    )
    (net (code "70") (name "/INPUT_6") (class "Default")
      (node (ref "P6") (pin "6") (pinfunction "6_6") (pintype "passive"))
      (node (ref "U1") (pin "7") (pinfunction "PC13/RTC_AF1_7") (pintype "passive"))
    )
    (net (code "71") (name "/INPUT_7") (class "Default")
      (node (ref "P6") (pin "7") (pinfunction "7_7") (pintype "passive"))
      (node (ref "U1") (pin "10") (pinfunction "PF0/FSMC_A0/I2C2_SDA_10") (pintype "passive"))
    )
    (net (code "72") (name "/INPUT_8") (class "Default")
      (node (ref "P6") (pin "8") (pinfunction "8_8") (pintype "passive"))
      (node (ref "U1") (pin "11") (pinfunction "PF1/FSMC_A1/I2C2_SCL_11") (pintype "passive"))
    )
    (net (code "73") (name "/INPUT_9") (class "Default")
      (node (ref "P6") (pin "9") (pinfunction "9_9") (pintype "passive"))
      (node (ref "U1") (pin "12") (pinfunction "PF2/FSMC_A2/I2C2_SMBA_12") (pintype "passive"))
    )
    (net (code "74") (name "/INPUT_10") (class "Default")
      (node (ref "P6") (pin "10") (pinfunction "10_10") (pintype "passive"))
      (node (ref "U1") (pin "13") (pinfunction "PF3/FSMC_A3/ADC3_IN9_13") (pintype "passive"))
    )
    (net (code "75") (name "/INPUT_11") (class "Default")
      (node (ref "P6") (pin "11") (pinfunction "11_11") (pintype "passive"))
      (node (ref "U1") (pin "14") (pinfunction "PF4/FSMC_A4/ADC3_IN14_14") (pintype "passive"))
    )
    (net (code "76") (name "/INPUT_12") (class "Default")
      (node (ref "P6") (pin "12") (pinfunction "12_12") (pintype "passive"))
      (node (ref "U1") (pin "15") (pinfunction "PF5/FSMC_A5/ADC3_IN15_15") (pintype "passive"))
    )
    (net (code "77") (name "/INPUT_13") (class "Default")
      (node (ref "P6") (pin "13") (pinfunction "13_13") (pintype "passive"))
      (node (ref "U1") (pin "18") (pinfunction "PF6/TIM10_CH1/FSMC_NIORD/ADC3_IN4_18") (pintype "passive"))
    )
    (net (code "78") (name "/INPUT_14") (class "Default")
      (node (ref "P6") (pin "14") (pinfunction "14_14") (pintype "passive"))
      (node (ref "U1") (pin "19") (pinfunction "PF7/TIM11_CH1/FSMC_NREG/ADC3_IN5_19") (pintype "passive"))
    )
    (net (code "79") (name "/INPUT_15") (class "Default")
      (node (ref "P6") (pin "15") (pinfunction "15_15") (pintype "passive"))
      (node (ref "U1") (pin "20") (pinfunction "PF8/TIM13_CH1/FSMC_NIOWR/ADC3_IN6_20") (pintype "passive"))
    )
    (net (code "80") (name "/INPUT_16") (class "Default")
      (node (ref "P6") (pin "16") (pinfunction "16_16") (pintype "passive"))
      (node (ref "U1") (pin "21") (pinfunction "PF9/TIM14_CH1/FSMC_CD/ADC3_IN7_21") (pintype "passive"))
    )
    (net (code "81") (name "/INPUT_17") (class "Default")
      (node (ref "P6") (pin "17") (pinfunction "17_17") (pintype "passive"))
      (node (ref "U1") (pin "22") (pinfunction "PF10/FSMC_INTR/ADC3_IN8_22") (pintype "passive"))
    )
    (net (code "82") (name "/INPUT_18") (class "Default")
      (node (ref "P6") (pin "18") (pinfunction "18_18") (pintype "passive"))
      (node (ref "U1") (pin "26") (pinfunction "PC0/OTG_HS_ULPI_STP/ADC123_IN10_26") (pintype "passive"))
    )
    (net (code "83") (name "/INPUT_19") (class "Default")
      (node (ref "P6") (pin "19") (pinfunction "19_19") (pintype "passive"))
      (node (ref "U1") (pin "40") (pinfunction "PA4/SPI1_NSS/U2_CK/DCMI_HSYNC/OTG_HS_SOF/I2S3_WS/DAC1_OUT/ADC12_IN4_40") (pintype "passive"))
    )
    (net (code "84") (name "/INPUT_20") (class "Default")
      (node (ref "P6") (pin "20") (pinfunction "20_20") (pintype "passive"))
      (node (ref "U1") (pin "41") (pinfunction "PA5/SPI1_SCK/OTG_HS_ULPI_CK/TIM2_CH1_ETR/TIM8_CH1N/DAC2_OUT/ADC12_IN5_41") (pintype "passive"))
    )
    (net (code "85") (name "/INPUT_21") (class "Default")
      (node (ref "P6") (pin "21") (pinfunction "21_21") (pintype "passive"))
      (node (ref "U1") (pin "42") (pinfunction "PA6/SPI1_MISO/TIM1_BKIN/TIM3_CH1/TIM8_BKIN/TIM13_CH1/DCMI_PIXCLK/ADC12_IN6_42") (pintype "passive"))
    )
    (net (code "86") (name "/INPUT_22") (class "Default")
      (node (ref "P6") (pin "22") (pinfunction "22_22") (pintype "passive"))
      (node (ref "U1") (pin "43") (pinfunction "PA7/SPI1_MOSI/TIM1_CH1N/TIM3_CH2/TIM8_CH1N/TIM14_CH1/ETH_MII_RX_DV/ETH_RMII_CRS_DV/ADC12_IN7_43") (pintype "passive"))
    )
    (net (code "87") (name "/INPUT_23") (class "Default")
      (node (ref "P6") (pin "23") (pinfunction "23_23") (pintype "passive"))
      (node (ref "U1") (pin "44") (pinfunction "PC4/ETH_MII_RXD0/ETH_RMII_RXD0/ADC12_IN14_44") (pintype "passive"))
    )
    (net (code "88") (name "/INPUT_24") (class "Default")
      (node (ref "P6") (pin "24") (pinfunction "24_24") (pintype "passive"))
      (node (ref "U1") (pin "45") (pinfunction "PC5/ETH_MII_RXD1/ETH_RMII_RXD1/ADC12_IN15_45") (pintype "passive"))
    )
    (net (code "89") (name "/INPUT_25") (class "Default")
      (node (ref "P6") (pin "25") (pinfunction "25_25") (pintype "passive"))
      (node (ref "U1") (pin "46") (pinfunction "PB0/TIM1_CH2N/TIM3_CH3/TIM8_CH2N/OTG_HS_ULPI_D1/ETH_MII_RXD2/ADC12_IN8_46") (pintype "passive"))
    )
    (net (code "90") (name "/INPUT_26") (class "Default")
      (node (ref "P6") (pin "26") (pinfunction "26_26") (pintype "passive"))
      (node (ref "U1") (pin "47") (pinfunction "PB1/TIM1_CH3N/TIM3_CH4/TIM8_CH3N/OTG_HS_INTN/ETH_MII_RXD3/ADC12_IN9_47") (pintype "passive"))
    )
    (net (code "91") (name "/INPUT_26_B") (class "Default")
      (node (ref "P35") (pin "34") (pinfunction "34_34") (pintype "passive"))
    )
    (net (code "92") (name "/INPUT_27") (class "Default")
      (node (ref "P6") (pin "27") (pinfunction "27_27") (pintype "passive"))
      (node (ref "U1") (pin "49") (pinfunction "PF11/DCMI_D12_49") (pintype "passive"))
    )
    (net (code "93") (name "/INPUT_27_B") (class "Default")
      (node (ref "P35") (pin "35") (pinfunction "35_35") (pintype "passive"))
    )
    (net (code "94") (name "/INPUT_28") (class "Default")
      (node (ref "P6") (pin "28") (pinfunction "28_28") (pintype "passive"))
      (node (ref "U1") (pin "50") (pinfunction "PF12/FSMC_A6_50") (pintype "passive"))
    )
    (net (code "95") (name "/INPUT_28_B") (class "Default")
      (node (ref "P35") (pin "36") (pinfunction "36_36") (pintype "passive"))
    )
    (net (code "96") (name "/INPUT_29") (class "Default")
      (node (ref "P6") (pin "29") (pinfunction "29_29") (pintype "passive"))
      (node (ref "U1") (pin "53") (pinfunction "PF13/FSMC_A7_53") (pintype "passive"))
    )
    (net (code "97") (name "/INPUT_29_B") (class "Default")
      (node (ref "P35") (pin "37") (pinfunction "37_37") (pintype "passive"))
    )
    (net (code "98") (name "/INPUT_30") (class "Default")
      (node (ref "P6") (pin "30") (pinfunction "30_30") (pintype "passive"))
      (node (ref "U1") (pin "54") (pinfunction "PF14/FSMC_A8_54") (pintype "passive"))
    )
    (net (code "99") (name "/INPUT_30_B") (class "Default")
      (node (ref "P35") (pin "38") (pinfunction "38_38") (pintype "passive"))
    )
    (net (code "100") (name "/INPUT_31") (class "Default")
      (node (ref "P6") (pin "31") (pinfunction "31_31") (pintype "passive"))
      (node (ref "U1") (pin "55") (pinfunction "PF15/FSMC_A9_55") (pintype "passive"))
    )
    (net (code "101") (name "/INPUT_31_B") (class "Default")
      (node (ref "P35") (pin "39") (pinfunction "39_39") (pintype "passive"))
    )
    (net (code "102") (name "/INPUT_32") (class "Default")
      (node (ref "P6") (pin "32") (pinfunction "32_32") (pintype "passive"))
      (node (ref "U1") (pin "56") (pinfunction "PG0/FSMC_A10_56") (pintype "passive"))
    )
    (net (code "103") (name "/INPUT_33") (class "Default")
      (node (ref "P6") (pin "33") (pinfunction "33_33") (pintype "passive"))
      (node (ref "U1") (pin "57") (pinfunction "PG1/FSMC_A11_57") (pintype "passive"))
    )
    (net (code "104") (name "/INPUT_34") (class "Default")
      (node (ref "P6") (pin "34") (pinfunction "34_34") (pintype "passive"))
      (node (ref "U1") (pin "58") (pinfunction "PE7/FSMC_D4/TIM1_ETR_58") (pintype "passive"))
    )
    (net (code "105") (name "/INPUT_35") (class "Default")
      (node (ref "P6") (pin "35") (pinfunction "35_35") (pintype "passive"))
      (node (ref "U1") (pin "59") (pinfunction "PE8/FSMC_D5/TIM1_CH1N_59") (pintype "passive"))
    )
    (net (code "106") (name "/INPUT_36") (class "Default")
      (node (ref "P6") (pin "36") (pinfunction "36_36") (pintype "passive"))
      (node (ref "U1") (pin "60") (pinfunction "PE9/FSMC_D6/TIM1_CH1_60") (pintype "passive"))
    )
    (net (code "107") (name "/INPUT_37") (class "Default")
      (node (ref "P6") (pin "37") (pinfunction "37_37") (pintype "passive"))
      (node (ref "U1") (pin "63") (pinfunction "PE10/FSMC_D7/TIM1_CH2N_63") (pintype "passive"))
    )
    (net (code "108") (name "/INPUT_38") (class "Default")
      (node (ref "P6") (pin "38") (pinfunction "38_38") (pintype "passive"))
      (node (ref "U1") (pin "64") (pinfunction "PE11/FSMC_D8/TIM1_CH2_64") (pintype "passive"))
    )
    (net (code "109") (name "/INPUT_39") (class "Default")
      (node (ref "P6") (pin "39") (pinfunction "39_39") (pintype "passive"))
      (node (ref "U1") (pin "65") (pinfunction "PE12/FSMC_D9/TIM1_CH3N_65") (pintype "passive"))
    )
    (net (code "110") (name "/INPUT_40") (class "Default")
      (node (ref "P5") (pin "1") (pinfunction "1_1") (pintype "passive"))
      (node (ref "U1") (pin "66") (pinfunction "PE13/FSMC_D10/TIM1_CH3_66") (pintype "passive"))
    )
    (net (code "111") (name "/INPUT_41") (class "Default")
      (node (ref "P5") (pin "2") (pinfunction "2_2") (pintype "passive"))
      (node (ref "U1") (pin "67") (pinfunction "PE14/FSMC_D11/TIM1_CH4_67") (pintype "passive"))
    )
    (net (code "112") (name "/INPUT_42") (class "Default")
      (node (ref "P5") (pin "3") (pinfunction "3_3") (pintype "passive"))
      (node (ref "U1") (pin "68") (pinfunction "PE15/FSMC_D12/TIM1_BKIN_68") (pintype "passive"))
    )
    (net (code "113") (name "/INPUT_43") (class "Default")
      (node (ref "P5") (pin "4") (pinfunction "4_4") (pintype "passive"))
      (node (ref "U1") (pin "69") (pinfunction "PB10/SPI2_SCK/TIM2_CH3/U3_TX/I2C2_SCL/OTG_HS_ULPI_D3/I2S2_CK_69") (pintype "passive"))
    )
    (net (code "114") (name "/INPUT_44") (class "Default")
      (node (ref "P5") (pin "5") (pinfunction "5_5") (pintype "passive"))
      (node (ref "U1") (pin "70") (pinfunction "PB11/TIM2_CH4/U3_RX/I2C2_SDA/HS_ULPI_D4/ETH_MII_TX_EN/ETH_RMII_TX_EN_70") (pintype "passive"))
    )
    (net (code "115") (name "/LED1") (class "Default")
      (node (ref "D1") (pin "2") (pinfunction "K_2") (pintype "passive"))
      (node (ref "U1") (pin "139") (pinfunction "PB8/TIM4_CH3/TIM10_CH1/CAN1_RX/SDIO_D4/ETH_MII_TXD3/I2C1_SCL/DCMI_D6_139") (pintype "passive"))
    )
    (net (code "116") (name "/LED2") (class "Default")
      (node (ref "D2") (pin "2") (pinfunction "K_2") (pintype "passive"))
      (node (ref "U1") (pin "140") (pinfunction "PB9/TIM4_CH4/TIM11_CH1/CAN1_TX/SDIO_D5/SPI2_NSS/I2C1_SDA/DCMI_D7/I2S2_WS_140") (pintype "passive"))
    )
    (net (code "117") (name "/LED3") (class "Default")
      (node (ref "D4") (pin "2") (pinfunction "K_2") (pintype "passive"))
      (node (ref "U1") (pin "141") (pinfunction "PE0/TIM4_ETR/FSMC_NBL0/DCMI_D2_141") (pintype "passive"))
    )
    (net (code "118") (name "/LED4") (class "Default")
      (node (ref "D5") (pin "2") (pinfunction "K_2") (pintype "passive"))
      (node (ref "U1") (pin "142") (pinfunction "PE1/FSMC_NBL1/DCMI_D3_142") (pintype "passive"))
    )
    (net (code "119") (name "/PA0_RS485_TX1") (class "Default")
      (node (ref "U1") (pin "34") (pinfunction "PA0-WKUP/U2_CTS/U4_TX/ETH_MII_CRS/TIM2_CH1_ETR/TIM5_CH1/TIM8_ETR/ADC123_IN0_34") (pintype "passive"))
      (node (ref "U10") (pin "4") (pinfunction "DI_4") (pintype "passive"))
    )
    (net (code "120") (name "/PA1_RS485_RX1") (class "Default")
      (node (ref "U1") (pin "35") (pinfunction "PA1/U2_RTS/U4_RX/ETH_RMII_REF_CLK/ETH_MII_RX_CLK/TIM2_CH2/TIM5_CH2/ADC123_IN1_35") (pintype "passive"))
      (node (ref "U10") (pin "1") (pinfunction "RO_1") (pintype "passive"))
    )
    (net (code "121") (name "/PA2_RS485_RE1") (class "Default")
      (node (ref "U1") (pin "36") (pinfunction "PA2/U2_TX/TIM2_CH3/TIM5_CH3/TIM9_CH1/ETH_MDIO/ADC123_IN2_36") (pintype "passive"))
      (node (ref "U10") (pin "2") (pinfunction "RE_2") (pintype "passive"))
      (node (ref "U10") (pin "3") (pinfunction "DE_3") (pintype "passive"))
    )
    (net (code "122") (name "/PA9_U1_TX") (class "Default")
      (node (ref "P4") (pin "4") (pinfunction "4_4") (pintype "passive"))
      (node (ref "U1") (pin "101") (pinfunction "PA9/TIM1_CH2/U1_TX/I2C3_SMBA/OTG_FS_VBUS/DCMI_D0_101") (pintype "passive"))
    )
    (net (code "123") (name "/PA10_U1_RX") (class "Default")
      (node (ref "P4") (pin "3") (pinfunction "3_3") (pintype "passive"))
      (node (ref "U1") (pin "102") (pinfunction "PA10/TIM1_CH3/U1_RX/OTG_FS_ID/DCMI_D1_102") (pintype "passive"))
    )
    (net (code "124") (name "/PA13-JTMS") (class "Default")
      (node (ref "P2") (pin "2") (pinfunction "2_2") (pintype "passive"))
      (node (ref "R11") (pin "2") (pinfunction "2_2") (pintype "passive"))
      (node (ref "U1") (pin "105") (pinfunction "PA13/JTMS_SWDIO_105") (pintype "passive"))
    )
    (net (code "125") (name "/PA14-JTCK") (class "Default")
      (node (ref "P2") (pin "1") (pinfunction "1_1") (pintype "passive"))
      (node (ref "R10") (pin "2") (pinfunction "2_2") (pintype "passive"))
      (node (ref "U1") (pin "109") (pinfunction "PA14/JTCK_SWCLK_109") (pintype "passive"))
    )
    (net (code "126") (name "/PC6_U6_TX") (class "Default")
      (node (ref "P1") (pin "1") (pinfunction "1_1") (pintype "passive"))
      (node (ref "U1") (pin "96") (pinfunction "PC6/TIM3_CH1/TIM8_CH1/U6_TX/SDIO_D6/DCMI_D0/I2S2_MCK_96") (pintype "passive"))
    )
    (net (code "127") (name "/PC7_U6_RX") (class "Default")
      (node (ref "P1") (pin "8") (pinfunction "8_8") (pintype "passive"))
      (node (ref "U1") (pin "97") (pinfunction "PC7/TIM3_CH2/TIM8_CH2/U6_RX/SDIO_D7/DCMI_D1/I2S3_MCK_97") (pintype "passive"))
    )
    (net (code "128") (name "/PC8_SDIO_0") (class "Default")
      (node (ref "J1") (pin "7") (pinfunction "DAT0/DO_7") (pintype "passive"))
      (node (ref "R3") (pin "1") (pinfunction "1_1") (pintype "passive"))
      (node (ref "U1") (pin "98") (pinfunction "PC8/TIM3_CH3/TIM8_CH3/U6_CK/SDIO_D0/DCMI_D2_98") (pintype "passive"))
    )
    (net (code "129") (name "/PC9_SDIO_1") (class "Default")
      (node (ref "J1") (pin "8") (pinfunction "DAT1_8") (pintype "passive"))
      (node (ref "R5") (pin "1") (pinfunction "1_1") (pintype "passive"))
      (node (ref "U1") (pin "99") (pinfunction "PC9/TIM3_CH4/TIM8_CH4/I2C3_SDA/SDIO_D1/DCMI_D3/MCO2/I2S_CKIN_99") (pintype "passive"))
    )
    (net (code "130") (name "/PC10_SDIO_2") (class "Default")
      (node (ref "J1") (pin "1") (pinfunction "DAT2_1") (pintype "passive"))
      (node (ref "R6") (pin "1") (pinfunction "1_1") (pintype "passive"))
      (node (ref "U1") (pin "111") (pinfunction "PC10/SPI3_SCK/U3_TX/U4_TX/SDIO_D2/DCMI_D8/I2S3_CK_111") (pintype "passive"))
    )
    (net (code "131") (name "/PC11_SDIO_3") (class "Default")
      (node (ref "J1") (pin "2") (pinfunction "CD/DAT3/CS_2") (pintype "passive"))
      (node (ref "R7") (pin "1") (pinfunction "1_1") (pintype "passive"))
      (node (ref "U1") (pin "112") (pinfunction "PC11/SPI3_MISO/U3_RX/U4_RX/SDIO_D3/DCMI_D4/I2S3ext_SD_112") (pintype "passive"))
    )
    (net (code "132") (name "/PC12_SDIO_CK") (class "Default")
      (node (ref "J1") (pin "5") (pinfunction "CLK/SCLK_5") (pintype "passive"))
      (node (ref "U1") (pin "113") (pinfunction "PC12/SPI3_MOSI/U3_CK/U5_TX/SDIO_CK/DCMI_D9/I2S3_SD_113") (pintype "passive"))
    )
    (net (code "133") (name "/PD2_SDIO_CMD") (class "Default")
      (node (ref "J1") (pin "3") (pinfunction "CMD/DI_3") (pintype "passive"))
      (node (ref "R8") (pin "1") (pinfunction "1_1") (pintype "passive"))
      (node (ref "U1") (pin "116") (pinfunction "PD2/TIM3_ETR/U5_RX/SDIO_CMD/DCMI_D11_116") (pintype "passive"))
    )
    (net (code "134") (name "/PD5_U2_TX") (class "Default")
      (node (ref "U1") (pin "119") (pinfunction "PD5/FSMC_NWE/U2_TX_119") (pintype "passive"))
      (node (ref "U7") (pin "11") (pinfunction "DIN1_11") (pintype "passive"))
    )
    (net (code "135") (name "/PD6_U2_RX") (class "Default")
      (node (ref "U1") (pin "122") (pinfunction "PD6/FSMC_NWAIT/U2_RX_122") (pintype "passive"))
      (node (ref "U7") (pin "12") (pinfunction "ROUT1_12") (pintype "passive"))
    )
    (net (code "136") (name "/PD8_RS485_TX2") (class "Default")
      (node (ref "U1") (pin "77") (pinfunction "PD8/FSMC_D13/U3_TX_77") (pintype "passive"))
      (node (ref "U12") (pin "4") (pinfunction "DI_4") (pintype "passive"))
    )
    (net (code "137") (name "/PD9_RS485_RX2") (class "Default")
      (node (ref "U1") (pin "78") (pinfunction "PD9/FSMC_D14/U3_RX_78") (pintype "passive"))
      (node (ref "U12") (pin "1") (pinfunction "RO_1") (pintype "passive"))
    )
    (net (code "138") (name "/PD10_RS485_RE2") (class "Default")
      (node (ref "U1") (pin "79") (pinfunction "PD10/FSMC_D15/U3_CK_79") (pintype "passive"))
      (node (ref "U12") (pin "2") (pinfunction "RE_2") (pintype "passive"))
      (node (ref "U12") (pin "3") (pinfunction "DE_3") (pintype "passive"))
    )
    (net (code "139") (name "/POWER_ADC") (class "Default")
      (node (ref "U1") (pin "27") (pinfunction "PC1/ETH_MDC/ADC123_IN11_27") (pintype "passive"))
      (node (ref "U11") (pin "1") (pinfunction "1OUT_1") (pintype "passive"))
      (node (ref "U11") (pin "2") (pinfunction "-_2") (pintype "passive"))
    )
    (net (code "140") (name "/PWM1") (class "Default")
      (node (ref "P8") (pin "4") (pinfunction "4_4") (pintype "passive"))
      (node (ref "U1") (pin "81") (pinfunction "PD12/FSMC_A17/FSMC_ALE/TIM4_CH1/U3_RTS_81") (pintype "passive"))
    )
    (net (code "141") (name "/PWM2") (class "Default")
      (node (ref "P8") (pin "3") (pinfunction "3_3") (pintype "passive"))
      (node (ref "U1") (pin "82") (pinfunction "PD13/FSMC_A18/TIM4_CH2_82") (pintype "passive"))
    )
    (net (code "142") (name "/PWM3") (class "Default")
      (node (ref "P8") (pin "2") (pinfunction "2_2") (pintype "passive"))
      (node (ref "U1") (pin "85") (pinfunction "PD14/FSMC_D0/TIM4_CH3_85") (pintype "passive"))
    )
    (net (code "143") (name "/PWM4") (class "Default")
      (node (ref "P8") (pin "1") (pinfunction "1_1") (pintype "passive"))
      (node (ref "U1") (pin "86") (pinfunction "PD15/FSMC_D1/TIM4_CH4_86") (pintype "passive"))
    )
    (net (code "144") (name "/QYG_KC1") (class "Default")
      (node (ref "P7") (pin "32") (pinfunction "32_32") (pintype "passive"))
      (node (ref "U1") (pin "90") (pinfunction "PG5/FSMC_A15_90") (pintype "passive"))
    )
    (net (code "145") (name "/RESET") (class "Default")
      (node (ref "C1") (pin "1") (pintype "passive"))
      (node (ref "D9") (pin "1") (pintype "passive"))
      (node (ref "R4") (pin "1") (pintype "passive"))
      (node (ref "RESET1") (pin "1") (pinfunction "1_1") (pintype "passive"))
      (node (ref "U1") (pin "25") (pinfunction "NRST_25") (pintype "passive"))
    )
    (net (code "146") (name "/RS485_1A") (class "Default")
      (node (ref "P7") (pin "7") (pinfunction "7_7") (pintype "passive"))
      (node (ref "R32") (pin "1") (pintype "passive"))
      (node (ref "R33") (pin "1") (pintype "passive"))
      (node (ref "U10") (pin "6") (pinfunction "A_6") (pintype "passive"))
    )
    (net (code "147") (name "/RS485_1B") (class "Default")
      (node (ref "P7") (pin "8") (pinfunction "8_8") (pintype "passive"))
      (node (ref "R33") (pin "2") (pintype "passive"))
      (node (ref "R34") (pin "2") (pintype "passive"))
      (node (ref "U10") (pin "7") (pinfunction "B_7") (pintype "passive"))
    )
    (net (code "148") (name "/RS485_2A") (class "Default")
      (node (ref "P7") (pin "38") (pinfunction "38_38") (pintype "passive"))
      (node (ref "R37") (pin "1") (pintype "passive"))
      (node (ref "R38") (pin "1") (pintype "passive"))
      (node (ref "U12") (pin "6") (pinfunction "A_6") (pintype "passive"))
    )
    (net (code "149") (name "/RS485_2B") (class "Default")
      (node (ref "P7") (pin "37") (pinfunction "37_37") (pintype "passive"))
      (node (ref "R38") (pin "2") (pintype "passive"))
      (node (ref "R39") (pin "2") (pintype "passive"))
      (node (ref "U12") (pin "7") (pinfunction "B_7") (pintype "passive"))
    )
    (net (code "150") (name "/RTS") (class "Default")
      (node (ref "Q2") (pin "1") (pinfunction "E_1") (pintype "passive"))
      (node (ref "R29") (pin "2") (pintype "passive"))
      (node (ref "U14") (pin "24") (pinfunction "RTS_24") (pintype "passive"))
    )
    (net (code "151") (name "/RXD") (class "Default")
      (node (ref "P4") (pin "6") (pinfunction "6_6") (pintype "passive"))
      (node (ref "U14") (pin "25") (pinfunction "RXD_25") (pintype "passive"))
    )
    (net (code "152") (name "/SDCLK") (class "Default")
      (node (ref "J2") (pin "5") (pinfunction "CLK/SCLK_5") (pintype "passive"))
      (node (ref "R16") (pin "2") (pintype "passive"))
      (node (ref "U3") (pin "17") (pinfunction "GPIOA4_17") (pintype "bidirectional"))
    )
    (net (code "153") (name "/SDCMD") (class "Default")
      (node (ref "J2") (pin "3") (pinfunction "CMD/DI_3") (pintype "passive"))
      (node (ref "U3") (pin "18") (pinfunction "GPIOA5_18") (pintype "bidirectional"))
    )
    (net (code "154") (name "/SDDAT") (class "Default")
      (node (ref "J2") (pin "7") (pinfunction "DAT0/DO_7") (pintype "passive"))
      (node (ref "U3") (pin "19") (pinfunction "GPIOA6_19") (pintype "bidirectional"))
    )
    (net (code "155") (name "/SPE+") (class "Default")
      (node (ref "P7") (pin "5") (pinfunction "5_5") (pintype "passive"))
      (node (ref "U5") (pin "3") (pinfunction "OUT+_3") (pintype "passive"))
    )
    (net (code "156") (name "/SPE-") (class "Default")
      (node (ref "P7") (pin "6") (pinfunction "6_6") (pintype "passive"))
      (node (ref "U5") (pin "4") (pinfunction "OUT-_4") (pintype "passive"))
    )
    (net (code "157") (name "/SPI2_MISO") (class "Default")
      (node (ref "U1") (pin "75") (pinfunction "PB14/SPI2_MISO/TIM1_CH2N/TIM8_CH2N/TIM12_CH1/U3_RTS/OTG_HS_DM/I2S2ext_SD_75") (pintype "passive"))
      (node (ref "U9") (pin "2") (pinfunction "DO_2") (pintype "passive"))
    )
    (net (code "158") (name "/SPI2_MOSI") (class "Default")
      (node (ref "U1") (pin "76") (pinfunction "PB15/SPI2_MOSI/TIM1_CH3N/TIM8_CH3N/TIM12_CH2/OTG_HS_DP/I2S2_SD_76") (pintype "passive"))
      (node (ref "U9") (pin "5") (pinfunction "DI_5") (pintype "passive"))
    )
    (net (code "159") (name "/SPI2_SCK") (class "Default")
      (node (ref "U1") (pin "74") (pinfunction "PB13/SPI2_SCK/TIM1_CH1N/U3_CTS/CAN2_TX/OTG_HS_ULPI_D6/OTG_HS_VBUS/ETH_MII_TXD1/ETH_RMII_TXD1/I2S2_CK_74") (pintype "passive"))
      (node (ref "U9") (pin "6") (pinfunction "CLK_6") (pintype "passive"))
    )
    (net (code "160") (name "/SPICS") (class "Default")
      (node (ref "U3") (pin "9") (pinfunction "SPICS_9") (pintype "output"))
      (node (ref "U4") (pin "1") (pinfunction "~{CS}_1") (pintype "passive"))
    )
    (net (code "161") (name "/SPIDI") (class "Default")
      (node (ref "R23") (pin "1") (pintype "passive"))
      (node (ref "U4") (pin "2") (pinfunction "DO_2") (pintype "passive"))
    )
    (net (code "162") (name "/SPIDO") (class "Default")
      (node (ref "R23") (pin "2") (pintype "passive"))
      (node (ref "U3") (pin "11") (pinfunction "SPIDO_11") (pintype "output"))
      (node (ref "U4") (pin "5") (pinfunction "DI_5") (pintype "passive"))
    )
    (net (code "163") (name "/SPISCK") (class "Default")
      (node (ref "U3") (pin "12") (pinfunction "SPICLK_12") (pintype "output"))
      (node (ref "U4") (pin "6") (pinfunction "CLK_6") (pintype "passive"))
    )
    (net (code "164") (name "/SSD_KC1") (class "Default")
      (node (ref "P7") (pin "28") (pinfunction "28_28") (pintype "passive"))
      (node (ref "U1") (pin "100") (pinfunction "PA8/TIM1_CH1/U1_CK/I2C3_SCL/MCO1/OTG_FS_SOF_100") (pintype "passive"))
    )
    (net (code "165") (name "/SSD_KC2") (class "Default")
      (node (ref "P7") (pin "27") (pinfunction "27_27") (pintype "passive"))
      (node (ref "U1") (pin "110") (pinfunction "PA15/JTDI/SPI1_NSS/SPI3_NSS/TIM2_CH1_ETR/I2S3_WS_110") (pintype "passive"))
    )
    (net (code "166") (name "/SSD_KC3") (class "Default")
      (node (ref "P7") (pin "26") (pinfunction "26_26") (pintype "passive"))
      (node (ref "U1") (pin "114") (pinfunction "PD0/FSMC_D2/CAN1_RX_114") (pintype "passive"))
    )
    (net (code "167") (name "/TXD") (class "Default")
      (node (ref "P4") (pin "5") (pinfunction "5_5") (pintype "passive"))
      (node (ref "U14") (pin "26") (pinfunction "TXD_26") (pintype "passive"))
    )
    (net (code "168") (name "/TXX_KC1") (class "Default")
      (node (ref "P7") (pin "31") (pinfunction "31_31") (pintype "passive"))
      (node (ref "U1") (pin "91") (pinfunction "PG6/FSMC_INT2_91") (pintype "passive"))
    )
    (net (code "169") (name "/TXX_KC2") (class "Default")
      (node (ref "P7") (pin "30") (pinfunction "30_30") (pintype "passive"))
      (node (ref "U1") (pin "92") (pinfunction "PG7/FSMC_INT3/U6_CK_92") (pintype "passive"))
    )
    (net (code "170") (name "/TXX_KC3") (class "Default")
      (node (ref "P7") (pin "29") (pinfunction "29_29") (pintype "passive"))
      (node (ref "U1") (pin "93") (pinfunction "PG8/U6_RTS/ETH_PPS_OUT_93") (pintype "passive"))
    )
    (net (code "171") (name "/U2_RX") (class "Default")
      (node (ref "P7") (pin "3") (pinfunction "3_3") (pintype "passive"))
      (node (ref "U7") (pin "13") (pinfunction "RIN1_13") (pintype "passive"))
    )
    (net (code "172") (name "/U2_TX") (class "Default")
      (node (ref "P7") (pin "4") (pinfunction "4_4") (pintype "passive"))
      (node (ref "U7") (pin "14") (pinfunction "DOUT1_14") (pintype "passive"))
    )
    (net (code "173") (name "/USB+") (class "Default")
      (node (ref "U3") (pin "21") (pinfunction "USB+_21") (pintype "input"))
      (node (ref "USB_SLAVE1") (pin "3") (pinfunction "D+_3") (pintype "passive"))
    )
    (net (code "174") (name "/USB-") (class "Default")
      (node (ref "U3") (pin "20") (pinfunction "USB-_20") (pintype "input"))
      (node (ref "USB_SLAVE1") (pin "2") (pinfunction "D-_2") (pintype "passive"))
    )
    (net (code "175") (name "/VBAT") (class "Default")
      (node (ref "C31") (pin "2") (pintype "passive"))
      (node (ref "D6") (pin "2") (pintype "passive"))
      (node (ref "D7") (pin "2") (pintype "passive"))
      (node (ref "U1") (pin "6") (pinfunction "VBAT_6") (pintype "passive"))
    )
    (net (code "176") (name "/VDD") (class "Default")
      (node (ref "C32") (pin "1") (pintype "passive"))
      (node (ref "R31") (pin "2") (pintype "passive"))
      (node (ref "U14") (pin "6") (pinfunction "VDD_6") (pintype "passive"))
    )
    (net (code "177") (name "/YY_RXD") (class "Default")
      (node (ref "P4") (pin "2") (pinfunction "2_2") (pintype "passive"))
      (node (ref "U3") (pin "7") (pinfunction "RX_7") (pintype "input"))
    )
    (net (code "178") (name "/YY_TXD") (class "Default")
      (node (ref "P4") (pin "1") (pinfunction "1_1") (pintype "passive"))
      (node (ref "U3") (pin "6") (pinfunction "TX_6") (pintype "output"))
    )
    (net (code "179") (name "/iNPUT_25_B") (class "Default")
      (node (ref "P35") (pin "33") (pinfunction "33_33") (pintype "passive"))
    )
    (net (code "180") (name "GND") (class "Default")
      (node (ref "BT1") (pin "2") (pinfunction "-_2") (pintype "passive"))
      (node (ref "C1") (pin "2") (pintype "passive"))
      (node (ref "C10") (pin "1") (pintype "passive"))
      (node (ref "C11") (pin "2") (pintype "passive"))
      (node (ref "C12") (pin "2") (pintype "passive"))
      (node (ref "C13") (pin "2") (pintype "passive"))
      (node (ref "C14") (pin "2") (pintype "passive"))
      (node (ref "C15") (pin "2") (pintype "passive"))
      (node (ref "C17") (pin "2") (pinfunction "GND_2") (pintype "passive"))
      (node (ref "C18") (pin "1") (pintype "passive"))
      (node (ref "C19") (pin "1") (pintype "passive"))
      (node (ref "C20") (pin "1") (pintype "passive"))
      (node (ref "C21") (pin "1") (pintype "passive"))
      (node (ref "C22") (pin "1") (pintype "passive"))
      (node (ref "C23") (pin "1") (pintype "passive"))
      (node (ref "C24") (pin "1") (pintype "passive"))
      (node (ref "C25") (pin "1") (pintype "passive"))
      (node (ref "C26") (pin "1") (pintype "passive"))
      (node (ref "C27") (pin "1") (pintype "passive"))
      (node (ref "C28") (pin "1") (pintype "passive"))
      (node (ref "C29") (pin "1") (pintype "passive"))
      (node (ref "C3") (pin "1") (pintype "passive"))
      (node (ref "C30") (pin "1") (pintype "passive"))
      (node (ref "C31") (pin "1") (pintype "passive"))
      (node (ref "C32") (pin "2") (pintype "passive"))
      (node (ref "C34") (pin "2") (pinfunction "GND_2") (pintype "passive"))
      (node (ref "C35") (pin "1") (pintype "passive"))
      (node (ref "C36") (pin "1") (pintype "passive"))
      (node (ref "C38") (pin "2") (pinfunction "GND_2") (pintype "passive"))
      (node (ref "C4") (pin "1") (pintype "passive"))
      (node (ref "C40") (pin "1") (pintype "passive"))
      (node (ref "C42") (pin "2") (pinfunction "2_2") (pintype "passive"))
      (node (ref "C43") (pin "2") (pintype "passive"))
      (node (ref "C44") (pin "2") (pintype "passive"))
      (node (ref "C45") (pin "2") (pintype "passive"))
      (node (ref "C5") (pin "1") (pintype "passive"))
      (node (ref "C7") (pin "2") (pintype "passive"))
      (node (ref "C9") (pin "1") (pintype "passive"))
      (node (ref "D11") (pin "2") (pinfunction "A_2") (pintype "passive"))
      (node (ref "D8") (pin "2") (pinfunction "K_2") (pintype "passive"))
      (node (ref "H1") (pin "5") (pinfunction "5_5") (pintype "passive"))
      (node (ref "H1") (pin "6") (pinfunction "6_6") (pintype "passive"))
      (node (ref "J1") (pin "6") (pinfunction "VSS_6") (pintype "passive"))
      (node (ref "J1") (pin "9") (pinfunction "Cd_9") (pintype "passive"))
      (node (ref "J2") (pin "10") (pinfunction "GROUND_10") (pintype "passive"))
      (node (ref "J2") (pin "11") (pinfunction "GROUND_11") (pintype "passive"))
      (node (ref "J2") (pin "12") (pinfunction "GROUND_12") (pintype "passive"))
      (node (ref "J2") (pin "13") (pinfunction "GROUND_13") (pintype "passive"))
      (node (ref "J2") (pin "6") (pinfunction "VSS_6") (pintype "passive"))
      (node (ref "J3") (pin "1") (pinfunction "-VIN_1") (pintype "passive"))
      (node (ref "J3") (pin "5") (pinfunction "GND_5") (pintype "passive"))
      (node (ref "P1") (pin "4") (pinfunction "4_4") (pintype "passive"))
      (node (ref "P2") (pin "3") (pinfunction "3_3") (pintype "passive"))
      (node (ref "P6") (pin "40") (pinfunction "40_40") (pintype "passive"))
      (node (ref "P7") (pin "2") (pinfunction "2_2") (pintype "passive"))
      (node (ref "Q4") (pin "1") (pinfunction "E_1") (pintype "passive"))
      (node (ref "R10") (pin "1") (pinfunction "1_1") (pintype "passive"))
      (node (ref "R19") (pin "2") (pintype "passive"))
      (node (ref "R34") (pin "1") (pintype "passive"))
      (node (ref "R36") (pin "1") (pinfunction "1_1") (pintype "passive"))
      (node (ref "R39") (pin "1") (pintype "passive"))
      (node (ref "R41") (pin "1") (pintype "passive"))
      (node (ref "RESET1") (pin "2") (pinfunction "2_2") (pintype "passive"))
      (node (ref "U1") (pin "107") (pinfunction "VSS_107") (pintype "passive"))
      (node (ref "U1") (pin "120") (pinfunction "VSS_120") (pintype "passive"))
      (node (ref "U1") (pin "130") (pinfunction "VSS_130") (pintype "passive"))
      (node (ref "U1") (pin "16") (pinfunction "VSS_16") (pintype "passive"))
      (node (ref "U1") (pin "31") (pinfunction "VSSA_31") (pintype "passive"))
      (node (ref "U1") (pin "38") (pinfunction "VSS_38") (pintype "passive"))
      (node (ref "U1") (pin "51") (pinfunction "VSS_51") (pintype "passive"))
      (node (ref "U1") (pin "61") (pinfunction "VSS_61") (pintype "passive"))
      (node (ref "U1") (pin "83") (pinfunction "VSS_83") (pintype "passive"))
      (node (ref "U1") (pin "94") (pinfunction "VSS_94") (pintype "passive"))
      (node (ref "U10") (pin "5") (pinfunction "GND_5") (pintype "passive"))
      (node (ref "U11") (pin "11") (pinfunction "GND_11") (pintype "passive"))
      (node (ref "U12") (pin "5") (pinfunction "GND_5") (pintype "passive"))
      (node (ref "U14") (pin "3") (pinfunction "GND_3") (pintype "passive"))
      (node (ref "U3") (pin "24") (pinfunction "DACVSS_24") (pintype "passive"))
      (node (ref "U3") (pin "5") (pinfunction "VSS_5") (pintype "power_in"))
      (node (ref "U4") (pin "4") (pinfunction "GND_4") (pintype "passive"))
      (node (ref "U5") (pin "6") (pinfunction "PW-_6") (pintype "passive"))
      (node (ref "U6") (pin "3") (pinfunction "GND_3") (pintype "passive"))
      (node (ref "U6") (pin "5") (pinfunction "~{ON}/OUT_5") (pintype "passive"))
      (node (ref "U7") (pin "15") (pinfunction "GND_15") (pintype "passive"))
      (node (ref "U8") (pin "1") (pinfunction "GND_1") (pintype "passive"))
      (node (ref "U9") (pin "4") (pinfunction "GND_4") (pintype "passive"))
      (node (ref "USB1") (pin "5") (pinfunction "GND_5") (pintype "passive"))
      (node (ref "USB_SLAVE1") (pin "4") (pinfunction "NC_4") (pintype "passive"))
      (node (ref "USB_SLAVE1") (pin "5") (pinfunction "GND_5") (pintype "passive"))
    )
    (net (code "181") (name "Net-(BEEP1-G)") (class "Default")
      (node (ref "BEEP1") (pin "2") (pinfunction "G_2") (pintype "passive"))
      (node (ref "Q4") (pin "3") (pinfunction "C_3") (pintype "passive"))
    )
    (net (code "182") (name "Net-(BT1-+)") (class "Default")
      (node (ref "BT1") (pin "1") (pinfunction "+_1") (pintype "passive"))
      (node (ref "D7") (pin "1") (pintype "passive"))
    )
    (net (code "183") (name "Net-(C6-Pad2)") (class "Default")
      (node (ref "C6") (pin "2") (pintype "passive"))
      (node (ref "R13") (pin "1") (pintype "passive"))
    )
    (net (code "184") (name "Net-(C8-Pad2)") (class "Default")
      (node (ref "C8") (pin "2") (pintype "passive"))
      (node (ref "R14") (pin "1") (pintype "passive"))
    )
    (net (code "185") (name "Net-(D1-A)") (class "Default")
      (node (ref "D1") (pin "1") (pinfunction "A_1") (pintype "passive"))
      (node (ref "R17") (pin "1") (pintype "passive"))
    )
    (net (code "186") (name "Net-(D2-A)") (class "Default")
      (node (ref "D2") (pin "1") (pinfunction "A_1") (pintype "passive"))
      (node (ref "R18") (pin "1") (pintype "passive"))
    )
    (net (code "187") (name "Net-(D4-A)") (class "Default")
      (node (ref "D4") (pin "1") (pinfunction "A_1") (pintype "passive"))
      (node (ref "R21") (pin "1") (pintype "passive"))
    )
    (net (code "188") (name "Net-(D5-A)") (class "Default")
      (node (ref "D5") (pin "1") (pinfunction "A_1") (pintype "passive"))
      (node (ref "R22") (pin "1") (pintype "passive"))
    )
    (net (code "189") (name "Net-(D8-A)") (class "Default")
      (node (ref "D8") (pin "1") (pinfunction "A_1") (pintype "passive"))
      (node (ref "R25") (pin "2") (pintype "passive"))
    )
    (net (code "190") (name "Net-(D11-K)") (class "Default")
      (node (ref "D11") (pin "1") (pinfunction "K_1") (pintype "passive"))
      (node (ref "L1") (pin "1") (pinfunction "1_1") (pintype "passive"))
      (node (ref "U6") (pin "2") (pinfunction "OUTPUT_2") (pintype "passive"))
    )
    (net (code "191") (name "Net-(H1-Pad3)") (class "Default")
      (node (ref "H1") (pin "3") (pinfunction "3_3") (pintype "passive"))
      (node (ref "R1") (pin "2") (pintype "passive"))
    )
    (net (code "192") (name "Net-(H1-Pad4)") (class "Default")
      (node (ref "H1") (pin "4") (pinfunction "4_4") (pintype "passive"))
      (node (ref "R2") (pin "1") (pintype "passive"))
    )
    (net (code "193") (name "Net-(J2-Cd)") (class "Default")
      (node (ref "J2") (pin "9") (pinfunction "Cd_9") (pintype "passive"))
      (node (ref "R16") (pin "1") (pintype "passive"))
    )
    (net (code "194") (name "Net-(J2-VDD)") (class "Default")
      (node (ref "C7") (pin "1") (pintype "passive"))
      (node (ref "J2") (pin "4") (pinfunction "VDD_4") (pintype "passive"))
      (node (ref "R15") (pin "1") (pintype "passive"))
    )
    (net (code "195") (name "Net-(K1-TAP1)") (class "Default")
      (node (ref "K1") (pin "2") (pinfunction "TAP1_2") (pintype "passive"))
      (node (ref "U8") (pin "3") (pinfunction "IN_3") (pintype "passive"))
    )
    (net (code "196") (name "Net-(P3-Pad2)") (class "Default")
      (node (ref "P3") (pin "2") (pinfunction "2_2") (pintype "passive"))
      (node (ref "R30") (pin "2") (pintype "passive"))
    )
    (net (code "197") (name "Net-(Q2-B)") (class "Default")
      (node (ref "Q2") (pin "2") (pinfunction "B_2") (pintype "passive"))
      (node (ref "R28") (pin "1") (pintype "passive"))
    )
    (net (code "198") (name "Net-(Q2-C)") (class "Default")
      (node (ref "D9") (pin "2") (pintype "passive"))
      (node (ref "Q2") (pin "3") (pinfunction "C_3") (pintype "passive"))
      (node (ref "R26") (pin "1") (pintype "passive"))
    )
    (net (code "199") (name "Net-(Q3-B)") (class "Default")
      (node (ref "Q3") (pin "2") (pinfunction "B_2") (pintype "passive"))
      (node (ref "R29") (pin "1") (pintype "passive"))
    )
    (net (code "200") (name "Net-(Q3-C)") (class "Default")
      (node (ref "Q3") (pin "3") (pinfunction "C_3") (pintype "passive"))
      (node (ref "R30") (pin "1") (pintype "passive"))
    )
    (net (code "201") (name "Net-(Q4-B)") (class "Default")
      (node (ref "Q4") (pin "2") (pinfunction "B_2") (pintype "passive"))
      (node (ref "R40") (pin "2") (pintype "passive"))
      (node (ref "R41") (pin "2") (pintype "passive"))
    )
    (net (code "202") (name "Net-(U1-PC14-OSC32_IN)") (class "Default")
      (node (ref "C3") (pin "2") (pintype "passive"))
      (node (ref "U1") (pin "8") (pinfunction "PC14-OSC32_IN_8") (pintype "passive"))
      (node (ref "Y1") (pin "2") (pinfunction "OSC2_2") (pintype "passive"))
    )
    (net (code "203") (name "Net-(U1-PC15-OSC32_OUT)") (class "Default")
      (node (ref "C5") (pin "2") (pintype "passive"))
      (node (ref "U1") (pin "9") (pinfunction "PC15-OSC32_OUT_9") (pintype "passive"))
      (node (ref "Y1") (pin "1") (pinfunction "OSC1_1") (pintype "passive"))
    )
    (net (code "204") (name "Net-(U1-PDR_ON)") (class "Default")
      (node (ref "R19") (pin "1") (pintype "passive"))
      (node (ref "R20") (pin "1") (pintype "passive"))
      (node (ref "U1") (pin "143") (pinfunction "PDR_ON_143") (pintype "passive"))
    )
    (net (code "205") (name "Net-(U1-PH0-OSC_IN)") (class "Default")
      (node (ref "C4") (pin "2") (pintype "passive"))
      (node (ref "R12") (pin "2") (pintype "passive"))
      (node (ref "U1") (pin "23") (pinfunction "PH0-OSC_IN_23") (pintype "passive"))
      (node (ref "Y2") (pin "2") (pinfunction "OSC2_2") (pintype "passive"))
    )
    (net (code "206") (name "Net-(U1-PH1-OSC_OUT)") (class "Default")
      (node (ref "C10") (pin "2") (pintype "passive"))
      (node (ref "R12") (pin "1") (pintype "passive"))
      (node (ref "U1") (pin "24") (pinfunction "PH1-OSC_OUT_24") (pintype "passive"))
      (node (ref "Y2") (pin "1") (pinfunction "OSC1_1") (pintype "passive"))
    )
    (net (code "207") (name "Net-(U1-Vcap_1)") (class "Default")
      (node (ref "C13") (pin "1") (pintype "passive"))
      (node (ref "U1") (pin "71") (pinfunction "Vcap_1_71") (pintype "passive"))
    )
    (net (code "208") (name "Net-(U1-Vcap_2)") (class "Default")
      (node (ref "C14") (pin "1") (pintype "passive"))
      (node (ref "U1") (pin "106") (pinfunction "Vcap_2_106") (pintype "passive"))
    )
    (net (code "209") (name "Net-(U3-DACL)") (class "Default")
      (node (ref "C6") (pin "1") (pintype "passive"))
      (node (ref "U3") (pin "1") (pinfunction "DACL_1") (pintype "output"))
    )
    (net (code "210") (name "Net-(U3-DACR)") (class "Default")
      (node (ref "C8") (pin "1") (pintype "passive"))
      (node (ref "U3") (pin "2") (pinfunction "DACR_2") (pintype "output"))
    )
    (net (code "211") (name "Net-(U3-GPIOA3)") (class "Default")
      (node (ref "R9") (pin "1") (pintype "passive"))
      (node (ref "U3") (pin "16") (pinfunction "GPIOA3_16") (pintype "bidirectional"))
    )
    (net (code "212") (name "Net-(U3-VCOM)") (class "Default")
      (node (ref "C9") (pin "2") (pintype "passive"))
      (node (ref "U3") (pin "23") (pinfunction "VCOM_23") (pintype "passive"))
    )
    (net (code "213") (name "Net-(U7-C1+)") (class "Default")
      (node (ref "C37") (pin "1") (pinfunction "1_1") (pintype "passive"))
      (node (ref "U7") (pin "1") (pinfunction "C1+_1") (pintype "passive"))
    )
    (net (code "214") (name "Net-(U7-C1-)") (class "Default")
      (node (ref "C37") (pin "2") (pinfunction "2_2") (pintype "passive"))
      (node (ref "U7") (pin "3") (pinfunction "C1-_3") (pintype "passive"))
    )
    (net (code "215") (name "Net-(U7-C2+)") (class "Default")
      (node (ref "C41") (pin "1") (pinfunction "1_1") (pintype "passive"))
      (node (ref "U7") (pin "4") (pinfunction "C2+_4") (pintype "passive"))
    )
    (net (code "216") (name "Net-(U7-C2-)") (class "Default")
      (node (ref "C41") (pin "2") (pinfunction "2_2") (pintype "passive"))
      (node (ref "U7") (pin "5") (pinfunction "C2-_5") (pintype "passive"))
    )
    (net (code "217") (name "Net-(U7-V+)") (class "Default")
      (node (ref "C39") (pin "1") (pinfunction "1_1") (pintype "passive"))
      (node (ref "U7") (pin "2") (pinfunction "V+_2") (pintype "passive"))
    )
    (net (code "218") (name "Net-(U7-V-)") (class "Default")
      (node (ref "C42") (pin "1") (pinfunction "1_1") (pintype "passive"))
      (node (ref "U7") (pin "6") (pinfunction "V-_6") (pintype "passive"))
    )
    (net (code "219") (name "Net-(U11A-+)") (class "Default")
      (node (ref "R35") (pin "1") (pinfunction "1_1") (pintype "passive"))
      (node (ref "R36") (pin "2") (pinfunction "2_2") (pintype "passive"))
      (node (ref "U11") (pin "3") (pinfunction "+_3") (pintype "passive"))
    )
    (net (code "220") (name "Net-(U14-D+)") (class "Default")
      (node (ref "U14") (pin "4") (pinfunction "D+_4") (pintype "passive"))
      (node (ref "USB1") (pin "3") (pinfunction "D+_3") (pintype "passive"))
    )
    (net (code "221") (name "Net-(U14-D-)") (class "Default")
      (node (ref "U14") (pin "5") (pinfunction "D-_5") (pintype "passive"))
      (node (ref "USB1") (pin "2") (pinfunction "D-_2") (pintype "passive"))
    )
    (net (code "222") (name "Net-(U14-REGIN)") (class "Default")
      (node (ref "C35") (pin "2") (pintype "passive"))
      (node (ref "U14") (pin "7") (pinfunction "REGIN_7") (pintype "passive"))
      (node (ref "U14") (pin "8") (pinfunction "VBUS_8") (pintype "passive"))
      (node (ref "USB1") (pin "1") (pinfunction "VCC_1") (pintype "passive"))
    )
    (net (code "223") (name "Net-(U14-RST)") (class "Default")
      (node (ref "R31") (pin "1") (pintype "passive"))
      (node (ref "U14") (pin "9") (pinfunction "RST_9") (pintype "passive"))
    )
    (net (code "224") (name "Net-(USB_SLAVE1-VCC)") (class "Default")
      (node (ref "D3") (pin "1") (pintype "passive"))
      (node (ref "USB_SLAVE1") (pin "1") (pinfunction "VCC_1") (pintype "passive"))
    )
    (net (code "225") (name "V33") (class "Default")
      (node (ref "C12") (pin "1") (pintype "passive"))
      (node (ref "C15") (pin "1") (pintype "passive"))
      (node (ref "R15") (pin "2") (pintype "passive"))
      (node (ref "R9") (pin "2") (pintype "passive"))
      (node (ref "U3") (pin "3") (pinfunction "VDDIO_3") (pintype "power_in"))
      (node (ref "U4") (pin "3") (pinfunction "~{WP}_3") (pintype "passive"))
      (node (ref "U4") (pin "7") (pinfunction "~{HOLD}_7") (pintype "passive"))
      (node (ref "U4") (pin "8") (pinfunction "VCC_8") (pintype "passive"))
    )
    (net (code "226") (name "VCC") (class "Default")
      (node (ref "D10") (pin "1") (pintype "passive"))
      (node (ref "J3") (pin "3") (pinfunction "+V0_3") (pintype "passive"))
      (node (ref "K1") (pin "3") (pinfunction "I/O1_3") (pintype "passive"))
      (node (ref "P8") (pin "6") (pinfunction "6_6") (pintype "passive"))
      (node (ref "U11") (pin "4") (pinfunction "VCC_4") (pintype "passive"))
    )
    (net (code "227") (name "VCC3.3") (class "Default")
      (node (ref "BEEP1") (pin "1") (pinfunction "P_1") (pintype "passive"))
      (node (ref "C19") (pin "2") (pintype "passive"))
      (node (ref "C20") (pin "2") (pintype "passive"))
      (node (ref "C21") (pin "2") (pintype "passive"))
      (node (ref "C22") (pin "2") (pintype "passive"))
      (node (ref "C23") (pin "2") (pintype "passive"))
      (node (ref "C24") (pin "2") (pintype "passive"))
      (node (ref "C25") (pin "2") (pintype "passive"))
      (node (ref "C26") (pin "2") (pintype "passive"))
      (node (ref "C27") (pin "2") (pintype "passive"))
      (node (ref "C28") (pin "2") (pintype "passive"))
      (node (ref "C29") (pin "2") (pintype "passive"))
      (node (ref "C30") (pin "2") (pintype "passive"))
      (node (ref "C36") (pin "2") (pintype "passive"))
      (node (ref "C38") (pin "1") (pinfunction "VCC_1") (pintype "passive"))
      (node (ref "C39") (pin "2") (pinfunction "2_2") (pintype "passive"))
      (node (ref "C40") (pin "2") (pintype "passive"))
      (node (ref "C43") (pin "1") (pintype "passive"))
      (node (ref "C44") (pin "1") (pintype "passive"))
      (node (ref "C45") (pin "1") (pintype "passive"))
      (node (ref "D6") (pin "1") (pintype "passive"))
      (node (ref "H1") (pin "1") (pinfunction "1_1") (pintype "passive"))
      (node (ref "H1") (pin "2") (pinfunction "2_2") (pintype "passive"))
      (node (ref "J1") (pin "4") (pinfunction "VDD_4") (pintype "passive"))
      (node (ref "P1") (pin "5") (pinfunction "5_5") (pintype "passive"))
      (node (ref "P1") (pin "7") (pinfunction "7_7") (pintype "passive"))
      (node (ref "P2") (pin "4") (pinfunction "4_4") (pintype "passive"))
      (node (ref "P7") (pin "36") (pinfunction "36_36") (pintype "passive"))
      (node (ref "P8") (pin "5") (pinfunction "5_5") (pintype "passive"))
      (node (ref "Q3") (pin "1") (pinfunction "E_1") (pintype "passive"))
      (node (ref "R11") (pin "1") (pinfunction "1_1") (pintype "passive"))
      (node (ref "R17") (pin "2") (pintype "passive"))
      (node (ref "R18") (pin "2") (pintype "passive"))
      (node (ref "R20") (pin "2") (pintype "passive"))
      (node (ref "R21") (pin "2") (pintype "passive"))
      (node (ref "R22") (pin "2") (pintype "passive"))
      (node (ref "R25") (pin "1") (pintype "passive"))
      (node (ref "R26") (pin "2") (pintype "passive"))
      (node (ref "R3") (pin "2") (pinfunction "2_2") (pintype "passive"))
      (node (ref "R32") (pin "2") (pintype "passive"))
      (node (ref "R37") (pin "2") (pintype "passive"))
      (node (ref "R4") (pin "2") (pintype "passive"))
      (node (ref "R5") (pin "2") (pinfunction "2_2") (pintype "passive"))
      (node (ref "R6") (pin "2") (pinfunction "2_2") (pintype "passive"))
      (node (ref "R7") (pin "2") (pinfunction "2_2") (pintype "passive"))
      (node (ref "R8") (pin "2") (pinfunction "2_2") (pintype "passive"))
      (node (ref "U1") (pin "108") (pinfunction "VDD_108") (pintype "passive"))
      (node (ref "U1") (pin "121") (pinfunction "VDD_121") (pintype "passive"))
      (node (ref "U1") (pin "131") (pinfunction "VDD_131") (pintype "passive"))
      (node (ref "U1") (pin "144") (pinfunction "VDD_144") (pintype "passive"))
      (node (ref "U1") (pin "17") (pinfunction "VDD_17") (pintype "passive"))
      (node (ref "U1") (pin "30") (pinfunction "VDD_30") (pintype "passive"))
      (node (ref "U1") (pin "32") (pinfunction "Vref+_32") (pintype "passive"))
      (node (ref "U1") (pin "33") (pinfunction "VDDA_33") (pintype "passive"))
      (node (ref "U1") (pin "39") (pinfunction "VDD_39") (pintype "passive"))
      (node (ref "U1") (pin "52") (pinfunction "VDD_52") (pintype "passive"))
      (node (ref "U1") (pin "62") (pinfunction "VDD_62") (pintype "passive"))
      (node (ref "U1") (pin "72") (pinfunction "VDD_72") (pintype "passive"))
      (node (ref "U1") (pin "84") (pinfunction "VDD_84") (pintype "passive"))
      (node (ref "U1") (pin "95") (pinfunction "VDD_95") (pintype "passive"))
      (node (ref "U10") (pin "8") (pinfunction "VCC_8") (pintype "passive"))
      (node (ref "U12") (pin "8") (pinfunction "VCC_8") (pintype "passive"))
      (node (ref "U7") (pin "16") (pinfunction "VCC_16") (pintype "passive"))
      (node (ref "U8") (pin "2") (pinfunction "OUT_2") (pintype "passive"))
      (node (ref "U8") (pin "4") (pinfunction "OUT_4") (pintype "passive"))
      (node (ref "U9") (pin "3") (pinfunction "~{WP}_3") (pintype "passive"))
      (node (ref "U9") (pin "7") (pinfunction "~{HOLD}_7") (pintype "passive"))
      (node (ref "U9") (pin "8") (pinfunction "VCC_8") (pintype "passive"))
    )
    (net (code "228") (name "VCC12") (class "Default")
      (node (ref "C34") (pin "1") (pinfunction "VCC_1") (pintype "passive"))
      (node (ref "L1") (pin "2") (pinfunction "2_2") (pintype "passive"))
      (node (ref "U5") (pin "5") (pinfunction "PW+_5") (pintype "passive"))
      (node (ref "U6") (pin "4") (pinfunction "FeedBack_4") (pintype "passive"))
    )
    (net (code "229") (name "VCC24") (class "Default")
      (node (ref "C17") (pin "1") (pinfunction "VCC_1") (pintype "passive"))
      (node (ref "C18") (pin "2") (pintype "passive"))
      (node (ref "J3") (pin "2") (pinfunction "+VIN_2") (pintype "passive"))
      (node (ref "P7") (pin "1") (pinfunction "1_1") (pintype "passive"))
      (node (ref "R35") (pin "2") (pinfunction "2_2") (pintype "passive"))
      (node (ref "U6") (pin "1") (pinfunction "+VIN_1") (pintype "passive"))
    )
    (net (code "230") (name "VMCU") (class "Default")
      (node (ref "C11") (pin "1") (pintype "passive"))
      (node (ref "D10") (pin "2") (pintype "passive"))
      (node (ref "D3") (pin "2") (pintype "passive"))
      (node (ref "U3") (pin "4") (pinfunction "VDD_4") (pintype "power_in"))
    )
    (net (code "231") (name "unconnected-(J1-GROUND-Pad10)") (class "Default")
      (node (ref "J1") (pin "10") (pinfunction "GROUND_10") (pintype "passive"))
    )
    (net (code "232") (name "unconnected-(J1-GROUND-Pad11)") (class "Default")
      (node (ref "J1") (pin "11") (pinfunction "GROUND_11") (pintype "passive"))
    )
    (net (code "233") (name "unconnected-(J1-GROUND-Pad12)") (class "Default")
      (node (ref "J1") (pin "12") (pinfunction "GROUND_12") (pintype "passive"))
    )
    (net (code "234") (name "unconnected-(J1-GROUND-Pad13)") (class "Default")
      (node (ref "J1") (pin "13") (pinfunction "GROUND_13") (pintype "passive"))
    )
    (net (code "235") (name "unconnected-(J2-CD{slash}DAT3{slash}CS-Pad2)") (class "Default")
      (node (ref "J2") (pin "2") (pinfunction "CD/DAT3/CS_2") (pintype "passive"))
    )
    (net (code "236") (name "unconnected-(J2-DAT1-Pad8)") (class "Default")
      (node (ref "J2") (pin "8") (pinfunction "DAT1_8") (pintype "passive"))
    )
    (net (code "237") (name "unconnected-(J2-DAT2-Pad1)") (class "Default")
      (node (ref "J2") (pin "1") (pinfunction "DAT2_1") (pintype "passive"))
    )
    (net (code "238") (name "unconnected-(J3-NC-Pad4)") (class "Default")
      (node (ref "J3") (pin "4") (pinfunction "NC_4") (pintype "passive"))
    )
    (net (code "239") (name "unconnected-(K1-I{slash}O1-Pad1)") (class "Default")
      (node (ref "K1") (pin "1") (pinfunction "I/O1_1") (pintype "passive"))
    )
    (net (code "240") (name "unconnected-(K1-I{slash}O2-Pad4)") (class "Default")
      (node (ref "K1") (pin "4") (pinfunction "I/O2_4") (pintype "passive"))
    )
    (net (code "241") (name "unconnected-(K1-I{slash}O2-Pad6)") (class "Default")
      (node (ref "K1") (pin "6") (pinfunction "I/O2_6") (pintype "passive"))
    )
    (net (code "242") (name "unconnected-(K1-TAP2-Pad5)") (class "Default")
      (node (ref "K1") (pin "5") (pinfunction "TAP2_5") (pintype "passive"))
    )
    (net (code "243") (name "unconnected-(P1-Pad2)") (class "Default")
      (node (ref "P1") (pin "2") (pinfunction "2_2") (pintype "passive"))
    )
    (net (code "244") (name "unconnected-(P1-Pad3)") (class "Default")
      (node (ref "P1") (pin "3") (pinfunction "3_3") (pintype "passive"))
    )
    (net (code "245") (name "unconnected-(P1-Pad6)") (class "Default")
      (node (ref "P1") (pin "6") (pinfunction "6_6") (pintype "passive"))
    )
    (net (code "246") (name "unconnected-(P5-Pad6)") (class "Default")
      (node (ref "P5") (pin "6") (pinfunction "6_6") (pintype "passive"))
    )
    (net (code "247") (name "unconnected-(U1-PD7{slash}FSMC_NE1{slash}FSMC_NCE2{slash}U2_CK-Pad123)") (class "Default")
      (node (ref "U1") (pin "123") (pinfunction "PD7/FSMC_NE1/FSMC_NCE2/U2_CK_123") (pintype "passive"))
    )
    (net (code "248") (name "unconnected-(U1-PD11{slash}FSMC_A16{slash}FSMC_CLE{slash}U3_CTS-Pad80)") (class "Default")
      (node (ref "U1") (pin "80") (pinfunction "PD11/FSMC_A16/FSMC_CLE/U3_CTS_80") (pintype "passive"))
    )
    (net (code "249") (name "unconnected-(U3-BUSY-Pad10)") (class "Default")
      (node (ref "U3") (pin "10") (pinfunction "BUSY_10") (pintype "passive"))
    )
    (net (code "250") (name "unconnected-(U3-GPIOA0-Pad13)") (class "Default")
      (node (ref "U3") (pin "13") (pinfunction "GPIOA0_13") (pintype "bidirectional"))
    )
    (net (code "251") (name "unconnected-(U3-GPIOA1-Pad14)") (class "Default")
      (node (ref "U3") (pin "14") (pinfunction "GPIOA1_14") (pintype "bidirectional"))
    )
    (net (code "252") (name "unconnected-(U3-GPIOA2-Pad15)") (class "Default")
      (node (ref "U3") (pin "15") (pinfunction "GPIOA2_15") (pintype "bidirectional"))
    )
    (net (code "253") (name "unconnected-(U3-GPIOA7-Pad8)") (class "Default")
      (node (ref "U3") (pin "8") (pinfunction "GPIOA7_8") (pintype "bidirectional"))
    )
    (net (code "254") (name "unconnected-(U3-NC-Pad22)") (class "Default")
      (node (ref "U3") (pin "22") (pinfunction "NC_22") (pintype "passive"))
    )
    (net (code "255") (name "unconnected-(U7-DIN2-Pad10)") (class "Default")
      (node (ref "U7") (pin "10") (pinfunction "DIN2_10") (pintype "passive"))
    )
    (net (code "256") (name "unconnected-(U7-DOUT2-Pad7)") (class "Default")
      (node (ref "U7") (pin "7") (pinfunction "DOUT2_7") (pintype "passive"))
    )
    (net (code "257") (name "unconnected-(U7-RIN2-Pad8)") (class "Default")
      (node (ref "U7") (pin "8") (pinfunction "RIN2_8") (pintype "passive"))
    )
    (net (code "258") (name "unconnected-(U7-ROUT2-Pad9)") (class "Default")
      (node (ref "U7") (pin "9") (pinfunction "ROUT2_9") (pintype "passive"))
    )
    (net (code "259") (name "unconnected-(U14-CTS-Pad23)") (class "Default")
      (node (ref "U14") (pin "23") (pinfunction "CTS_23") (pintype "passive"))
    )
    (net (code "260") (name "unconnected-(U14-DCD-Pad1)") (class "Default")
      (node (ref "U14") (pin "1") (pinfunction "DCD_1") (pintype "passive"))
    )
    (net (code "261") (name "unconnected-(U14-DSR-Pad27)") (class "Default")
      (node (ref "U14") (pin "27") (pinfunction "DSR_27") (pintype "passive"))
    )
    (net (code "262") (name "unconnected-(U14-NC-Pad10)") (class "Default")
      (node (ref "U14") (pin "10") (pinfunction "NC_10") (pintype "passive"))
    )
    (net (code "263") (name "unconnected-(U14-NC-Pad13)") (class "Default")
      (node (ref "U14") (pin "13") (pinfunction "NC_13") (pintype "passive"))
    )
    (net (code "264") (name "unconnected-(U14-NC-Pad14)") (class "Default")
      (node (ref "U14") (pin "14") (pinfunction "NC_14") (pintype "passive"))
    )
    (net (code "265") (name "unconnected-(U14-NC-Pad15)") (class "Default")
      (node (ref "U14") (pin "15") (pinfunction "NC_15") (pintype "passive"))
    )
    (net (code "266") (name "unconnected-(U14-NC-Pad16)") (class "Default")
      (node (ref "U14") (pin "16") (pinfunction "NC_16") (pintype "passive"))
    )
    (net (code "267") (name "unconnected-(U14-NC-Pad17)") (class "Default")
      (node (ref "U14") (pin "17") (pinfunction "NC_17") (pintype "passive"))
    )
    (net (code "268") (name "unconnected-(U14-NC-Pad18)") (class "Default")
      (node (ref "U14") (pin "18") (pinfunction "NC_18") (pintype "passive"))
    )
    (net (code "269") (name "unconnected-(U14-NC-Pad19)") (class "Default")
      (node (ref "U14") (pin "19") (pinfunction "NC_19") (pintype "passive"))
    )
    (net (code "270") (name "unconnected-(U14-NC-Pad20)") (class "Default")
      (node (ref "U14") (pin "20") (pinfunction "NC_20") (pintype "passive"))
    )
    (net (code "271") (name "unconnected-(U14-NC-Pad21)") (class "Default")
      (node (ref "U14") (pin "21") (pinfunction "NC_21") (pintype "passive"))
    )
    (net (code "272") (name "unconnected-(U14-NC-Pad22)") (class "Default")
      (node (ref "U14") (pin "22") (pinfunction "NC_22") (pintype "passive"))
    )
    (net (code "273") (name "unconnected-(U14-RI-Pad2)") (class "Default")
      (node (ref "U14") (pin "2") (pinfunction "RI_2") (pintype "passive"))
    )
    (net (code "274") (name "unconnected-(U14-SUNPEND-Pad12)") (class "Default")
      (node (ref "U14") (pin "12") (pinfunction "SUNPEND_12") (pintype "passive"))
    )
    (net (code "275") (name "unconnected-(U14-~{SUSPEN}D-Pad11)") (class "Default")
      (node (ref "U14") (pin "11") (pinfunction "~{SUSPEN}D_11") (pintype "passive"))
    )
    (net (code "276") (name "unconnected-(USB1-NC-Pad4)") (class "Default")
      (node (ref "USB1") (pin "4") (pinfunction "NC_4") (pintype "passive"))
    )
  )
)
